# 12.net
KiCad netlist of a schematic drawn in Altium Designer
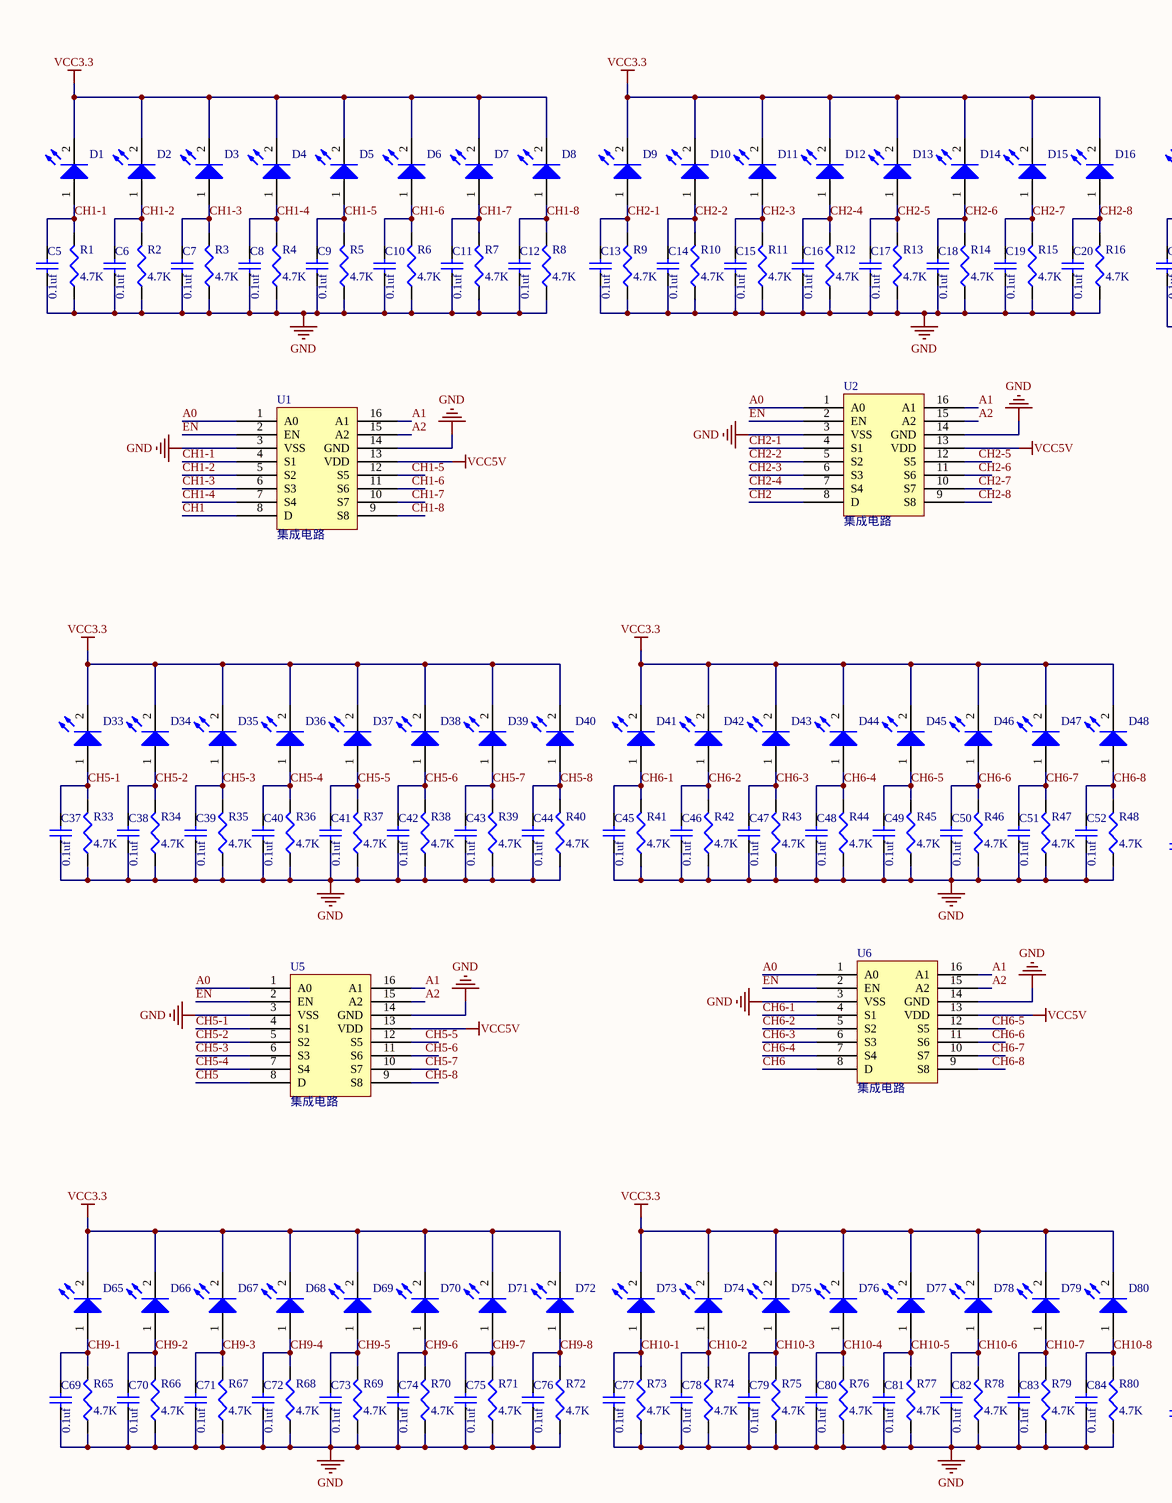
[diagram p0: 数粒机接收板12通道.SchDoc, top left]
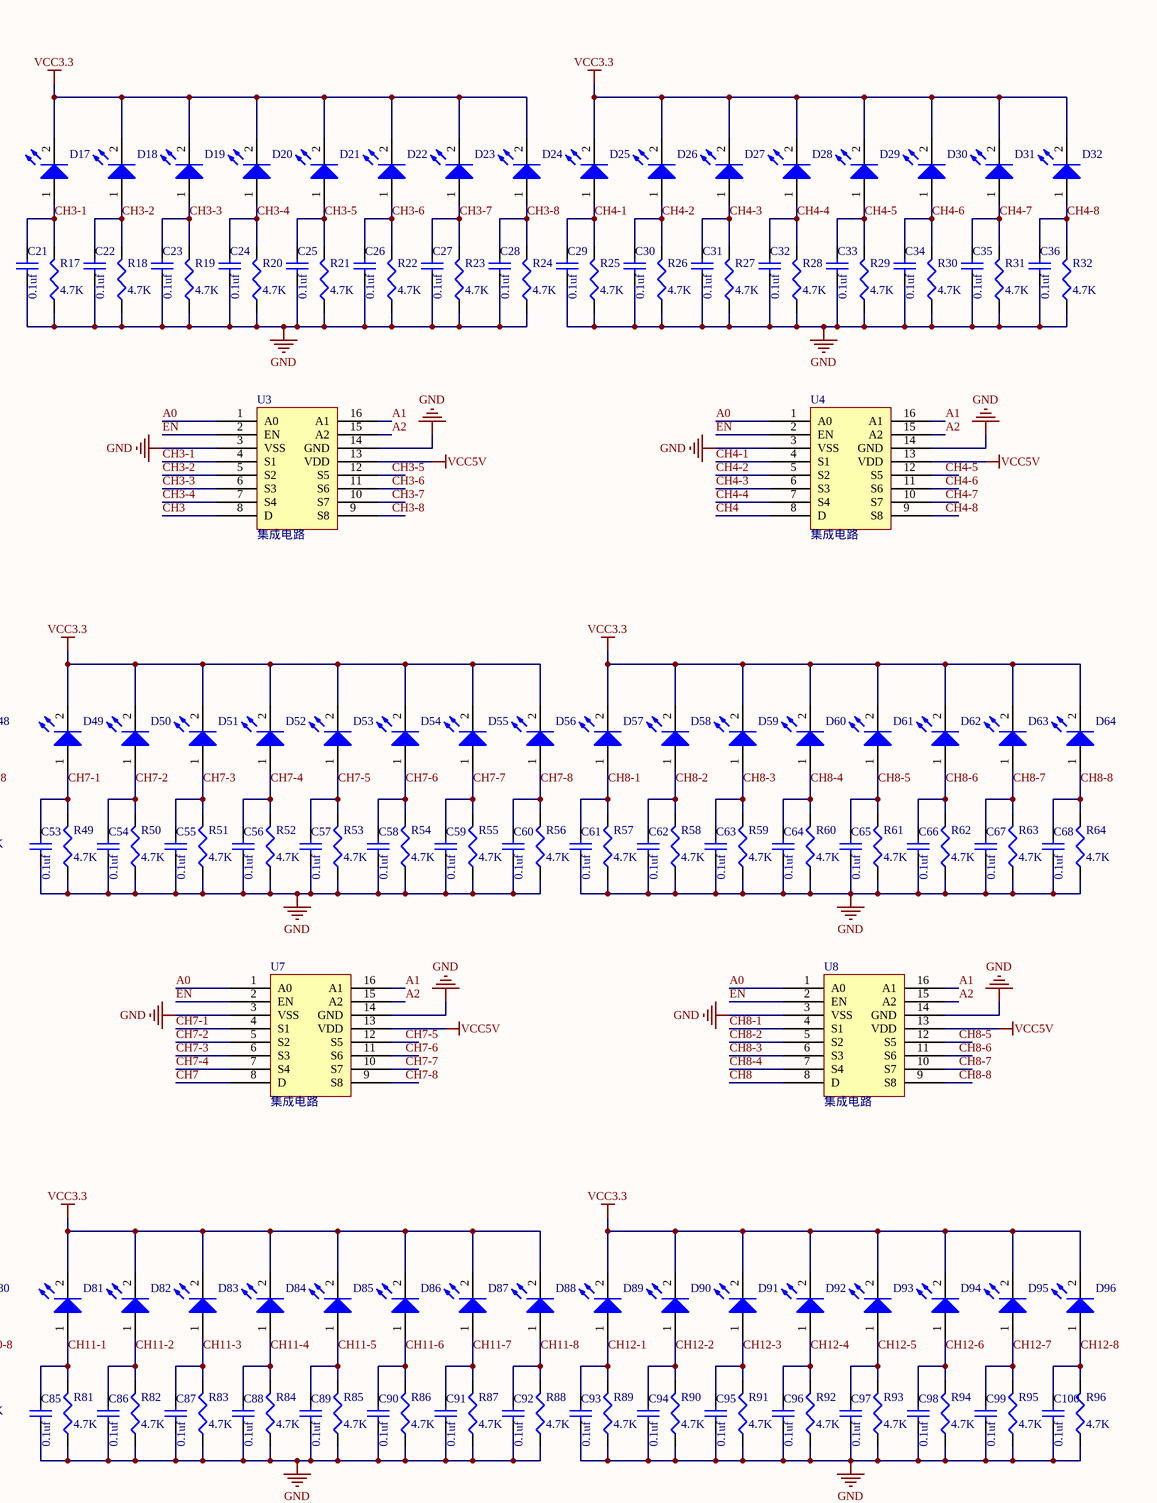
[diagram p1: 数粒机接收板12通道.SchDoc, top right]
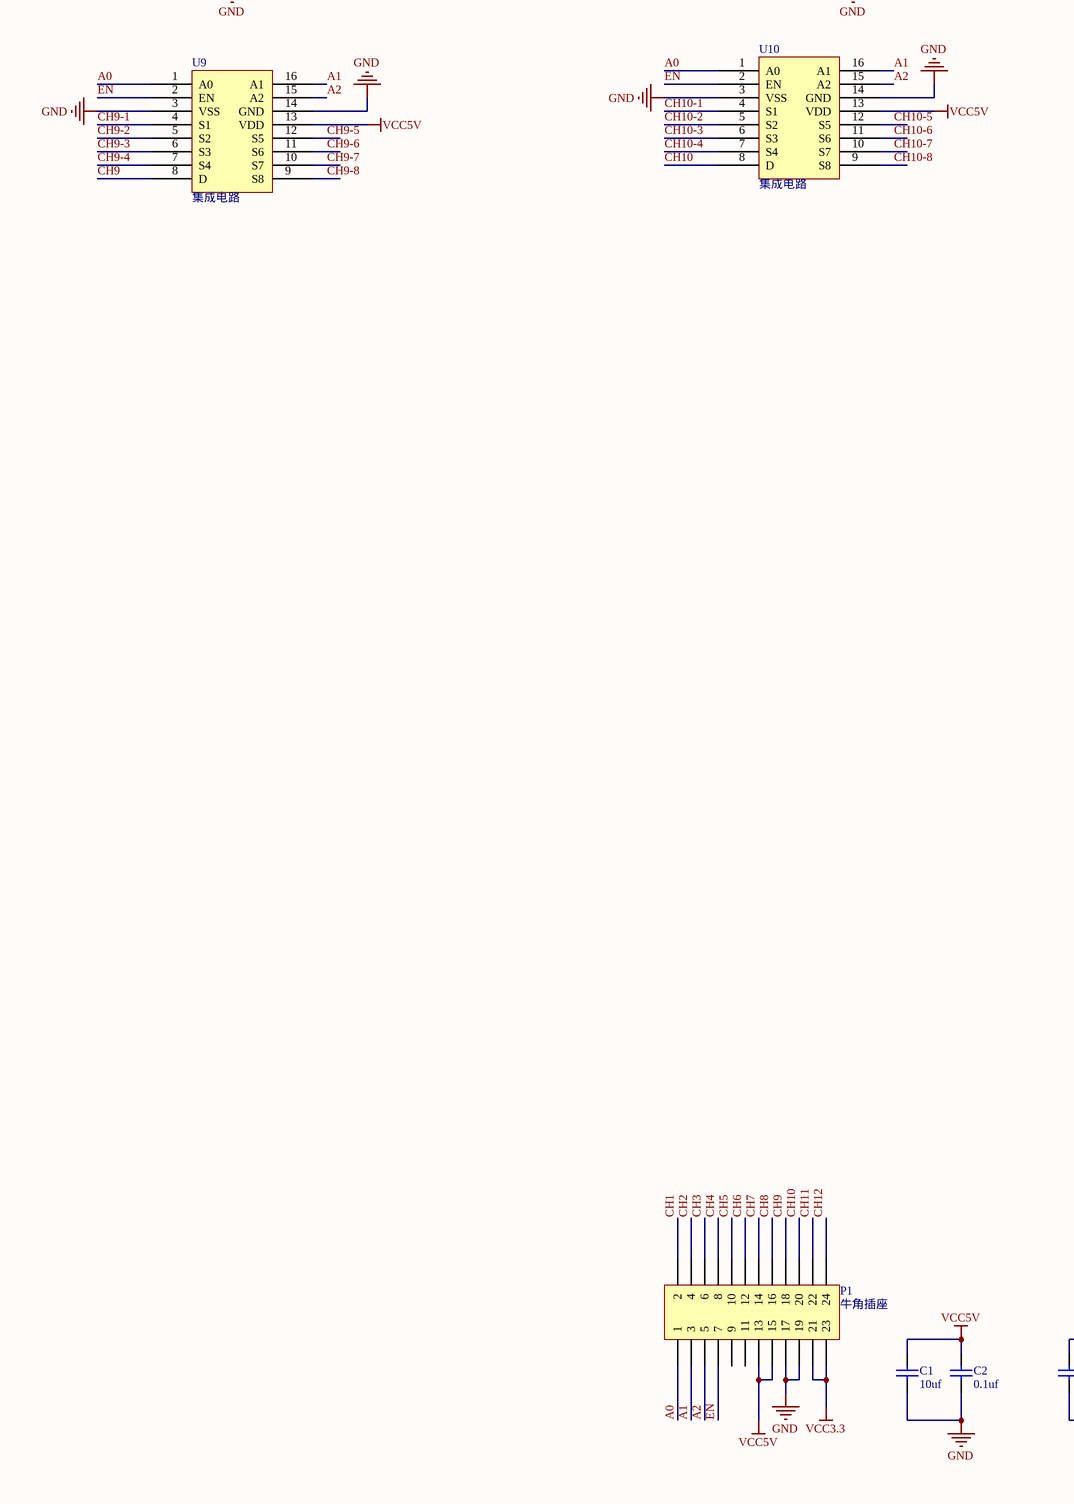
[diagram p2: 数粒机接收板12通道.SchDoc, bottom left]
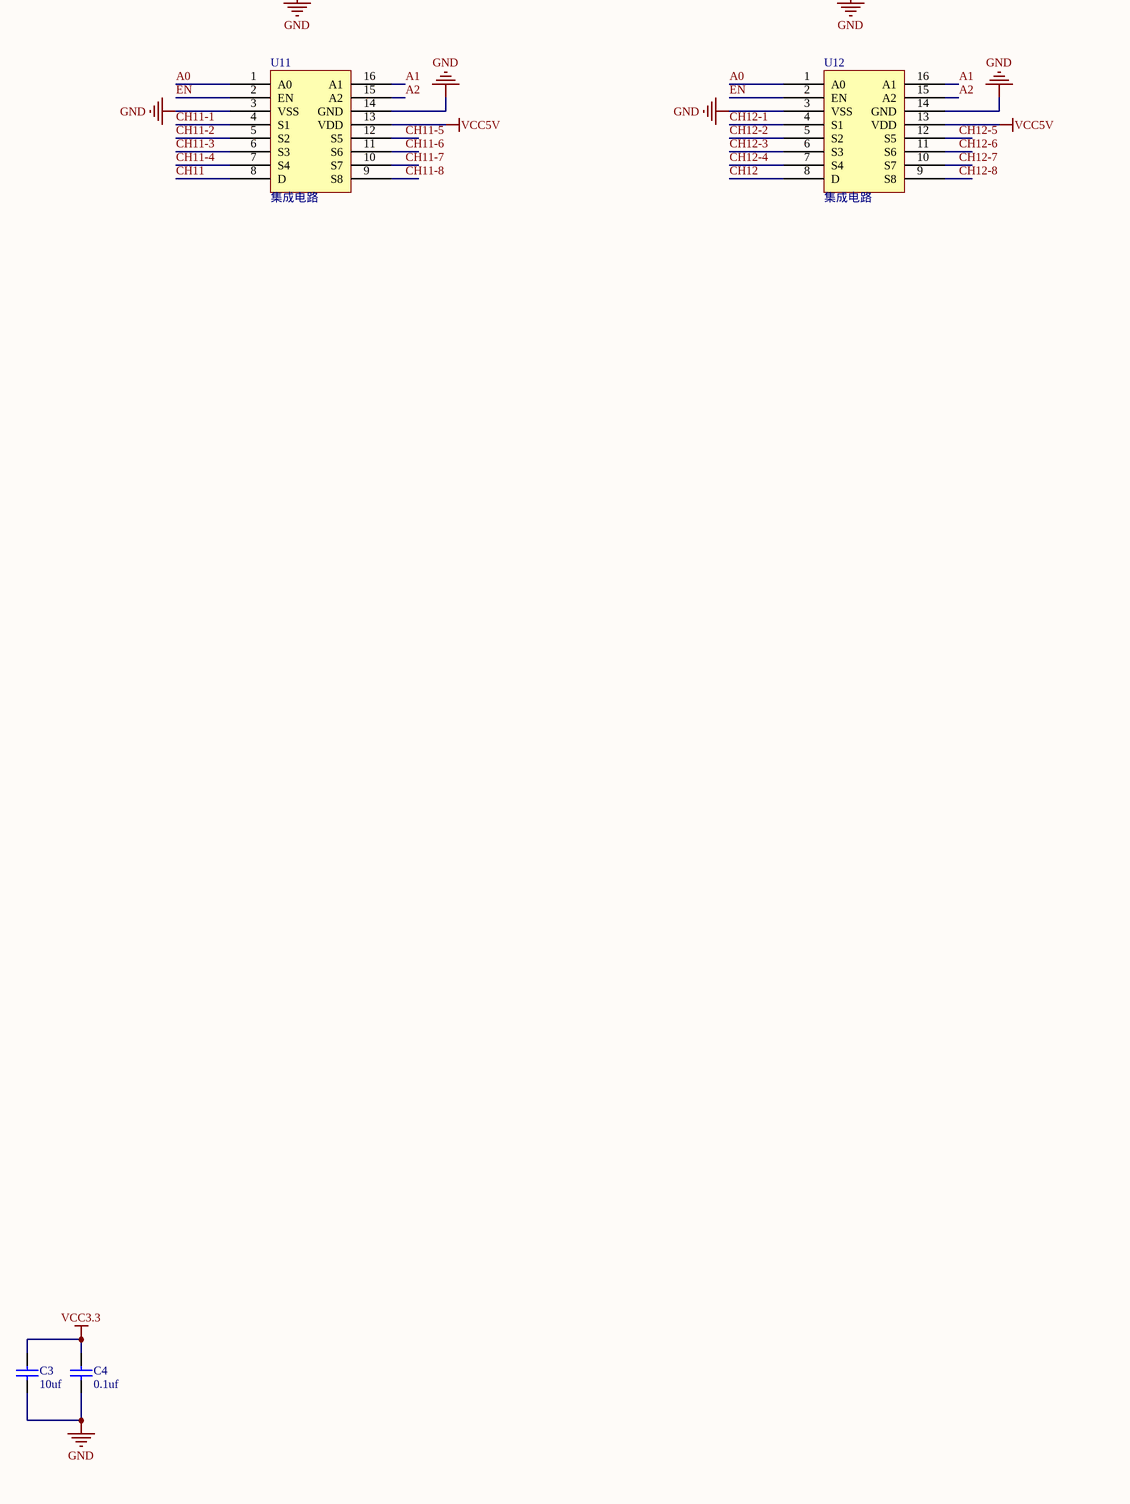
[diagram p3: 数粒机接收板12通道.SchDoc, bottom right]

(export (version "E")
  (design (tool "Eeschema 10.0.6"))
  (components
    (comp (ref "C1")
      (value "10uf")
      (footprint "0805c")
      (description "Capacitor 10uf")
      (fields (field (name "Comment") "贴片电容 10uf") (field (name "PUBLISHER") "Altium Limited"))
      (libsource (lib "Miscellaneous Devices") (part "Cap"))
    )
    (comp (ref "C2")
      (value "0.1uf")
      (footprint "0805c")
      (description "Capacitor 0.1uf")
      (fields (field (name "Comment") "贴片电容 0.1uf") (field (name "PUBLISHER") "Altium Limited"))
      (libsource (lib "Miscellaneous Devices") (part "Cap"))
    )
    (comp (ref "C3")
      (value "10uf")
      (footprint "0805c")
      (description "Capacitor 10uf")
      (fields (field (name "Comment") "贴片电容 10uf") (field (name "PUBLISHER") "Altium Limited"))
      (libsource (lib "Miscellaneous Devices") (part "Cap"))
    )
    (comp (ref "C4")
      (value "0.1uf")
      (footprint "0805c")
      (description "Capacitor 0.1uf")
      (fields (field (name "Comment") "贴片电容 0.1uf") (field (name "PUBLISHER") "Altium Limited"))
      (libsource (lib "Miscellaneous Devices") (part "Cap"))
    )
    (comp (ref "C5")
      (value "0.1uf")
      (footprint "0805c")
      (description "Capacitor 0.1uf")
      (fields (field (name "Comment") "贴片电容 0.1uf") (field (name "PUBLISHER") "Altium Limited"))
      (libsource (lib "Miscellaneous Devices") (part "Cap"))
    )
    (comp (ref "C6")
      (value "0.1uf")
      (footprint "0805c")
      (description "Capacitor 0.1uf")
      (fields (field (name "Comment") "贴片电容 0.1uf") (field (name "PUBLISHER") "Altium Limited"))
      (libsource (lib "Miscellaneous Devices") (part "Cap"))
    )
    (comp (ref "C7")
      (value "0.1uf")
      (footprint "0805c")
      (description "Capacitor 0.1uf")
      (fields (field (name "Comment") "贴片电容 0.1uf") (field (name "PUBLISHER") "Altium Limited"))
      (libsource (lib "Miscellaneous Devices") (part "Cap"))
    )
    (comp (ref "C8")
      (value "0.1uf")
      (footprint "0805c")
      (description "Capacitor 0.1uf")
      (fields (field (name "Comment") "贴片电容 0.1uf") (field (name "PUBLISHER") "Altium Limited"))
      (libsource (lib "Miscellaneous Devices") (part "Cap"))
    )
    (comp (ref "C9")
      (value "0.1uf")
      (footprint "0805c")
      (description "Capacitor 0.1uf")
      (fields (field (name "Comment") "贴片电容 0.1uf") (field (name "PUBLISHER") "Altium Limited"))
      (libsource (lib "Miscellaneous Devices") (part "Cap"))
    )
    (comp (ref "C10")
      (value "0.1uf")
      (footprint "0805c")
      (description "Capacitor 0.1uf")
      (fields (field (name "Comment") "贴片电容 0.1uf") (field (name "PUBLISHER") "Altium Limited"))
      (libsource (lib "Miscellaneous Devices") (part "Cap"))
    )
    (comp (ref "C11")
      (value "0.1uf")
      (footprint "0805c")
      (description "Capacitor 0.1uf")
      (fields (field (name "Comment") "贴片电容 0.1uf") (field (name "PUBLISHER") "Altium Limited"))
      (libsource (lib "Miscellaneous Devices") (part "Cap"))
    )
    (comp (ref "C12")
      (value "0.1uf")
      (footprint "0805c")
      (description "Capacitor 0.1uf")
      (fields (field (name "Comment") "贴片电容 0.1uf") (field (name "PUBLISHER") "Altium Limited"))
      (libsource (lib "Miscellaneous Devices") (part "Cap"))
    )
    (comp (ref "C13")
      (value "0.1uf")
      (footprint "0805c")
      (description "Capacitor 0.1uf")
      (fields (field (name "Comment") "贴片电容 0.1uf") (field (name "PUBLISHER") "Altium Limited"))
      (libsource (lib "Miscellaneous Devices") (part "Cap"))
    )
    (comp (ref "C14")
      (value "0.1uf")
      (footprint "0805c")
      (description "Capacitor 0.1uf")
      (fields (field (name "Comment") "贴片电容 0.1uf") (field (name "PUBLISHER") "Altium Limited"))
      (libsource (lib "Miscellaneous Devices") (part "Cap"))
    )
    (comp (ref "C15")
      (value "0.1uf")
      (footprint "0805c")
      (description "Capacitor 0.1uf")
      (fields (field (name "Comment") "贴片电容 0.1uf") (field (name "PUBLISHER") "Altium Limited"))
      (libsource (lib "Miscellaneous Devices") (part "Cap"))
    )
    (comp (ref "C16")
      (value "0.1uf")
      (footprint "0805c")
      (description "Capacitor 0.1uf")
      (fields (field (name "Comment") "贴片电容 0.1uf") (field (name "PUBLISHER") "Altium Limited"))
      (libsource (lib "Miscellaneous Devices") (part "Cap"))
    )
    (comp (ref "C17")
      (value "0.1uf")
      (footprint "0805c")
      (description "Capacitor 0.1uf")
      (fields (field (name "Comment") "贴片电容 0.1uf") (field (name "PUBLISHER") "Altium Limited"))
      (libsource (lib "Miscellaneous Devices") (part "Cap"))
    )
    (comp (ref "C18")
      (value "0.1uf")
      (footprint "0805c")
      (description "Capacitor 0.1uf")
      (fields (field (name "Comment") "贴片电容 0.1uf") (field (name "PUBLISHER") "Altium Limited"))
      (libsource (lib "Miscellaneous Devices") (part "Cap"))
    )
    (comp (ref "C19")
      (value "0.1uf")
      (footprint "0805c")
      (description "Capacitor 0.1uf")
      (fields (field (name "Comment") "贴片电容 0.1uf") (field (name "PUBLISHER") "Altium Limited"))
      (libsource (lib "Miscellaneous Devices") (part "Cap"))
    )
    (comp (ref "C20")
      (value "0.1uf")
      (footprint "0805c")
      (description "Capacitor 0.1uf")
      (fields (field (name "Comment") "贴片电容 0.1uf") (field (name "PUBLISHER") "Altium Limited"))
      (libsource (lib "Miscellaneous Devices") (part "Cap"))
    )
    (comp (ref "C21")
      (value "0.1uf")
      (footprint "0805c")
      (description "Capacitor 0.1uf")
      (fields (field (name "Comment") "贴片电容 0.1uf") (field (name "PUBLISHER") "Altium Limited"))
      (libsource (lib "Miscellaneous Devices") (part "Cap"))
    )
    (comp (ref "C22")
      (value "0.1uf")
      (footprint "0805c")
      (description "Capacitor 0.1uf")
      (fields (field (name "Comment") "贴片电容 0.1uf") (field (name "PUBLISHER") "Altium Limited"))
      (libsource (lib "Miscellaneous Devices") (part "Cap"))
    )
    (comp (ref "C23")
      (value "0.1uf")
      (footprint "0805c")
      (description "Capacitor 0.1uf")
      (fields (field (name "Comment") "贴片电容 0.1uf") (field (name "PUBLISHER") "Altium Limited"))
      (libsource (lib "Miscellaneous Devices") (part "Cap"))
    )
    (comp (ref "C24")
      (value "0.1uf")
      (footprint "0805c")
      (description "Capacitor 0.1uf")
      (fields (field (name "Comment") "贴片电容 0.1uf") (field (name "PUBLISHER") "Altium Limited"))
      (libsource (lib "Miscellaneous Devices") (part "Cap"))
    )
    (comp (ref "C25")
      (value "0.1uf")
      (footprint "0805c")
      (description "Capacitor 0.1uf")
      (fields (field (name "Comment") "贴片电容 0.1uf") (field (name "PUBLISHER") "Altium Limited"))
      (libsource (lib "Miscellaneous Devices") (part "Cap"))
    )
    (comp (ref "C26")
      (value "0.1uf")
      (footprint "0805c")
      (description "Capacitor 0.1uf")
      (fields (field (name "Comment") "贴片电容 0.1uf") (field (name "PUBLISHER") "Altium Limited"))
      (libsource (lib "Miscellaneous Devices") (part "Cap"))
    )
    (comp (ref "C27")
      (value "0.1uf")
      (footprint "0805c")
      (description "Capacitor 0.1uf")
      (fields (field (name "Comment") "贴片电容 0.1uf") (field (name "PUBLISHER") "Altium Limited"))
      (libsource (lib "Miscellaneous Devices") (part "Cap"))
    )
    (comp (ref "C28")
      (value "0.1uf")
      (footprint "0805c")
      (description "Capacitor 0.1uf")
      (fields (field (name "Comment") "贴片电容 0.1uf") (field (name "PUBLISHER") "Altium Limited"))
      (libsource (lib "Miscellaneous Devices") (part "Cap"))
    )
    (comp (ref "C29")
      (value "0.1uf")
      (footprint "0805c")
      (description "Capacitor 0.1uf")
      (fields (field (name "Comment") "贴片电容 0.1uf") (field (name "PUBLISHER") "Altium Limited"))
      (libsource (lib "Miscellaneous Devices") (part "Cap"))
    )
    (comp (ref "C30")
      (value "0.1uf")
      (footprint "0805c")
      (description "Capacitor 0.1uf")
      (fields (field (name "Comment") "贴片电容 0.1uf") (field (name "PUBLISHER") "Altium Limited"))
      (libsource (lib "Miscellaneous Devices") (part "Cap"))
    )
    (comp (ref "C31")
      (value "0.1uf")
      (footprint "0805c")
      (description "Capacitor 0.1uf")
      (fields (field (name "Comment") "贴片电容 0.1uf") (field (name "PUBLISHER") "Altium Limited"))
      (libsource (lib "Miscellaneous Devices") (part "Cap"))
    )
    (comp (ref "C32")
      (value "0.1uf")
      (footprint "0805c")
      (description "Capacitor 0.1uf")
      (fields (field (name "Comment") "贴片电容 0.1uf") (field (name "PUBLISHER") "Altium Limited"))
      (libsource (lib "Miscellaneous Devices") (part "Cap"))
    )
    (comp (ref "C33")
      (value "0.1uf")
      (footprint "0805c")
      (description "Capacitor 0.1uf")
      (fields (field (name "Comment") "贴片电容 0.1uf") (field (name "PUBLISHER") "Altium Limited"))
      (libsource (lib "Miscellaneous Devices") (part "Cap"))
    )
    (comp (ref "C34")
      (value "0.1uf")
      (footprint "0805c")
      (description "Capacitor 0.1uf")
      (fields (field (name "Comment") "贴片电容 0.1uf") (field (name "PUBLISHER") "Altium Limited"))
      (libsource (lib "Miscellaneous Devices") (part "Cap"))
    )
    (comp (ref "C35")
      (value "0.1uf")
      (footprint "0805c")
      (description "Capacitor 0.1uf")
      (fields (field (name "Comment") "贴片电容 0.1uf") (field (name "PUBLISHER") "Altium Limited"))
      (libsource (lib "Miscellaneous Devices") (part "Cap"))
    )
    (comp (ref "C36")
      (value "0.1uf")
      (footprint "0805c")
      (description "Capacitor 0.1uf")
      (fields (field (name "Comment") "贴片电容 0.1uf") (field (name "PUBLISHER") "Altium Limited"))
      (libsource (lib "Miscellaneous Devices") (part "Cap"))
    )
    (comp (ref "C37")
      (value "0.1uf")
      (footprint "0805c")
      (description "Capacitor 0.1uf")
      (fields (field (name "Comment") "贴片电容 0.1uf") (field (name "PUBLISHER") "Altium Limited"))
      (libsource (lib "Miscellaneous Devices") (part "Cap"))
    )
    (comp (ref "C38")
      (value "0.1uf")
      (footprint "0805c")
      (description "Capacitor 0.1uf")
      (fields (field (name "Comment") "贴片电容 0.1uf") (field (name "PUBLISHER") "Altium Limited"))
      (libsource (lib "Miscellaneous Devices") (part "Cap"))
    )
    (comp (ref "C39")
      (value "0.1uf")
      (footprint "0805c")
      (description "Capacitor 0.1uf")
      (fields (field (name "Comment") "贴片电容 0.1uf") (field (name "PUBLISHER") "Altium Limited"))
      (libsource (lib "Miscellaneous Devices") (part "Cap"))
    )
    (comp (ref "C40")
      (value "0.1uf")
      (footprint "0805c")
      (description "Capacitor 0.1uf")
      (fields (field (name "Comment") "贴片电容 0.1uf") (field (name "PUBLISHER") "Altium Limited"))
      (libsource (lib "Miscellaneous Devices") (part "Cap"))
    )
    (comp (ref "C41")
      (value "0.1uf")
      (footprint "0805c")
      (description "Capacitor 0.1uf")
      (fields (field (name "Comment") "贴片电容 0.1uf") (field (name "PUBLISHER") "Altium Limited"))
      (libsource (lib "Miscellaneous Devices") (part "Cap"))
    )
    (comp (ref "C42")
      (value "0.1uf")
      (footprint "0805c")
      (description "Capacitor 0.1uf")
      (fields (field (name "Comment") "贴片电容 0.1uf") (field (name "PUBLISHER") "Altium Limited"))
      (libsource (lib "Miscellaneous Devices") (part "Cap"))
    )
    (comp (ref "C43")
      (value "0.1uf")
      (footprint "0805c")
      (description "Capacitor 0.1uf")
      (fields (field (name "Comment") "贴片电容 0.1uf") (field (name "PUBLISHER") "Altium Limited"))
      (libsource (lib "Miscellaneous Devices") (part "Cap"))
    )
    (comp (ref "C44")
      (value "0.1uf")
      (footprint "0805c")
      (description "Capacitor 0.1uf")
      (fields (field (name "Comment") "贴片电容 0.1uf") (field (name "PUBLISHER") "Altium Limited"))
      (libsource (lib "Miscellaneous Devices") (part "Cap"))
    )
    (comp (ref "C45")
      (value "0.1uf")
      (footprint "0805c")
      (description "Capacitor 0.1uf")
      (fields (field (name "Comment") "贴片电容 0.1uf") (field (name "PUBLISHER") "Altium Limited"))
      (libsource (lib "Miscellaneous Devices") (part "Cap"))
    )
    (comp (ref "C46")
      (value "0.1uf")
      (footprint "0805c")
      (description "Capacitor 0.1uf")
      (fields (field (name "Comment") "贴片电容 0.1uf") (field (name "PUBLISHER") "Altium Limited"))
      (libsource (lib "Miscellaneous Devices") (part "Cap"))
    )
    (comp (ref "C47")
      (value "0.1uf")
      (footprint "0805c")
      (description "Capacitor 0.1uf")
      (fields (field (name "Comment") "贴片电容 0.1uf") (field (name "PUBLISHER") "Altium Limited"))
      (libsource (lib "Miscellaneous Devices") (part "Cap"))
    )
    (comp (ref "C48")
      (value "0.1uf")
      (footprint "0805c")
      (description "Capacitor 0.1uf")
      (fields (field (name "Comment") "贴片电容 0.1uf") (field (name "PUBLISHER") "Altium Limited"))
      (libsource (lib "Miscellaneous Devices") (part "Cap"))
    )
    (comp (ref "C49")
      (value "0.1uf")
      (footprint "0805c")
      (description "Capacitor 0.1uf")
      (fields (field (name "Comment") "贴片电容 0.1uf") (field (name "PUBLISHER") "Altium Limited"))
      (libsource (lib "Miscellaneous Devices") (part "Cap"))
    )
    (comp (ref "C50")
      (value "0.1uf")
      (footprint "0805c")
      (description "Capacitor 0.1uf")
      (fields (field (name "Comment") "贴片电容 0.1uf") (field (name "PUBLISHER") "Altium Limited"))
      (libsource (lib "Miscellaneous Devices") (part "Cap"))
    )
    (comp (ref "C51")
      (value "0.1uf")
      (footprint "0805c")
      (description "Capacitor 0.1uf")
      (fields (field (name "Comment") "贴片电容 0.1uf") (field (name "PUBLISHER") "Altium Limited"))
      (libsource (lib "Miscellaneous Devices") (part "Cap"))
    )
    (comp (ref "C52")
      (value "0.1uf")
      (footprint "0805c")
      (description "Capacitor 0.1uf")
      (fields (field (name "Comment") "贴片电容 0.1uf") (field (name "PUBLISHER") "Altium Limited"))
      (libsource (lib "Miscellaneous Devices") (part "Cap"))
    )
    (comp (ref "C53")
      (value "0.1uf")
      (footprint "0805c")
      (description "Capacitor 0.1uf")
      (fields (field (name "Comment") "贴片电容 0.1uf") (field (name "PUBLISHER") "Altium Limited"))
      (libsource (lib "Miscellaneous Devices") (part "Cap"))
    )
    (comp (ref "C54")
      (value "0.1uf")
      (footprint "0805c")
      (description "Capacitor 0.1uf")
      (fields (field (name "Comment") "贴片电容 0.1uf") (field (name "PUBLISHER") "Altium Limited"))
      (libsource (lib "Miscellaneous Devices") (part "Cap"))
    )
    (comp (ref "C55")
      (value "0.1uf")
      (footprint "0805c")
      (description "Capacitor 0.1uf")
      (fields (field (name "Comment") "贴片电容 0.1uf") (field (name "PUBLISHER") "Altium Limited"))
      (libsource (lib "Miscellaneous Devices") (part "Cap"))
    )
    (comp (ref "C56")
      (value "0.1uf")
      (footprint "0805c")
      (description "Capacitor 0.1uf")
      (fields (field (name "Comment") "贴片电容 0.1uf") (field (name "PUBLISHER") "Altium Limited"))
      (libsource (lib "Miscellaneous Devices") (part "Cap"))
    )
    (comp (ref "C57")
      (value "0.1uf")
      (footprint "0805c")
      (description "Capacitor 0.1uf")
      (fields (field (name "Comment") "贴片电容 0.1uf") (field (name "PUBLISHER") "Altium Limited"))
      (libsource (lib "Miscellaneous Devices") (part "Cap"))
    )
    (comp (ref "C58")
      (value "0.1uf")
      (footprint "0805c")
      (description "Capacitor 0.1uf")
      (fields (field (name "Comment") "贴片电容 0.1uf") (field (name "PUBLISHER") "Altium Limited"))
      (libsource (lib "Miscellaneous Devices") (part "Cap"))
    )
    (comp (ref "C59")
      (value "0.1uf")
      (footprint "0805c")
      (description "Capacitor 0.1uf")
      (fields (field (name "Comment") "贴片电容 0.1uf") (field (name "PUBLISHER") "Altium Limited"))
      (libsource (lib "Miscellaneous Devices") (part "Cap"))
    )
    (comp (ref "C60")
      (value "0.1uf")
      (footprint "0805c")
      (description "Capacitor 0.1uf")
      (fields (field (name "Comment") "贴片电容 0.1uf") (field (name "PUBLISHER") "Altium Limited"))
      (libsource (lib "Miscellaneous Devices") (part "Cap"))
    )
    (comp (ref "C61")
      (value "0.1uf")
      (footprint "0805c")
      (description "Capacitor 0.1uf")
      (fields (field (name "Comment") "贴片电容 0.1uf") (field (name "PUBLISHER") "Altium Limited"))
      (libsource (lib "Miscellaneous Devices") (part "Cap"))
    )
    (comp (ref "C62")
      (value "0.1uf")
      (footprint "0805c")
      (description "Capacitor 0.1uf")
      (fields (field (name "Comment") "贴片电容 0.1uf") (field (name "PUBLISHER") "Altium Limited"))
      (libsource (lib "Miscellaneous Devices") (part "Cap"))
    )
    (comp (ref "C63")
      (value "0.1uf")
      (footprint "0805c")
      (description "Capacitor 0.1uf")
      (fields (field (name "Comment") "贴片电容 0.1uf") (field (name "PUBLISHER") "Altium Limited"))
      (libsource (lib "Miscellaneous Devices") (part "Cap"))
    )
    (comp (ref "C64")
      (value "0.1uf")
      (footprint "0805c")
      (description "Capacitor 0.1uf")
      (fields (field (name "Comment") "贴片电容 0.1uf") (field (name "PUBLISHER") "Altium Limited"))
      (libsource (lib "Miscellaneous Devices") (part "Cap"))
    )
    (comp (ref "C65")
      (value "0.1uf")
      (footprint "0805c")
      (description "Capacitor 0.1uf")
      (fields (field (name "Comment") "贴片电容 0.1uf") (field (name "PUBLISHER") "Altium Limited"))
      (libsource (lib "Miscellaneous Devices") (part "Cap"))
    )
    (comp (ref "C66")
      (value "0.1uf")
      (footprint "0805c")
      (description "Capacitor 0.1uf")
      (fields (field (name "Comment") "贴片电容 0.1uf") (field (name "PUBLISHER") "Altium Limited"))
      (libsource (lib "Miscellaneous Devices") (part "Cap"))
    )
    (comp (ref "C67")
      (value "0.1uf")
      (footprint "0805c")
      (description "Capacitor 0.1uf")
      (fields (field (name "Comment") "贴片电容 0.1uf") (field (name "PUBLISHER") "Altium Limited"))
      (libsource (lib "Miscellaneous Devices") (part "Cap"))
    )
    (comp (ref "C68")
      (value "0.1uf")
      (footprint "0805c")
      (description "Capacitor 0.1uf")
      (fields (field (name "Comment") "贴片电容 0.1uf") (field (name "PUBLISHER") "Altium Limited"))
      (libsource (lib "Miscellaneous Devices") (part "Cap"))
    )
    (comp (ref "C69")
      (value "0.1uf")
      (footprint "0805c")
      (description "Capacitor 0.1uf")
      (fields (field (name "Comment") "贴片电容 0.1uf") (field (name "PUBLISHER") "Altium Limited"))
      (libsource (lib "Miscellaneous Devices") (part "Cap"))
    )
    (comp (ref "C70")
      (value "0.1uf")
      (footprint "0805c")
      (description "Capacitor 0.1uf")
      (fields (field (name "Comment") "贴片电容 0.1uf") (field (name "PUBLISHER") "Altium Limited"))
      (libsource (lib "Miscellaneous Devices") (part "Cap"))
    )
    (comp (ref "C71")
      (value "0.1uf")
      (footprint "0805c")
      (description "Capacitor 0.1uf")
      (fields (field (name "Comment") "贴片电容 0.1uf") (field (name "PUBLISHER") "Altium Limited"))
      (libsource (lib "Miscellaneous Devices") (part "Cap"))
    )
    (comp (ref "C72")
      (value "0.1uf")
      (footprint "0805c")
      (description "Capacitor 0.1uf")
      (fields (field (name "Comment") "贴片电容 0.1uf") (field (name "PUBLISHER") "Altium Limited"))
      (libsource (lib "Miscellaneous Devices") (part "Cap"))
    )
    (comp (ref "C73")
      (value "0.1uf")
      (footprint "0805c")
      (description "Capacitor 0.1uf")
      (fields (field (name "Comment") "贴片电容 0.1uf") (field (name "PUBLISHER") "Altium Limited"))
      (libsource (lib "Miscellaneous Devices") (part "Cap"))
    )
    (comp (ref "C74")
      (value "0.1uf")
      (footprint "0805c")
      (description "Capacitor 0.1uf")
      (fields (field (name "Comment") "贴片电容 0.1uf") (field (name "PUBLISHER") "Altium Limited"))
      (libsource (lib "Miscellaneous Devices") (part "Cap"))
    )
    (comp (ref "C75")
      (value "0.1uf")
      (footprint "0805c")
      (description "Capacitor 0.1uf")
      (fields (field (name "Comment") "贴片电容 0.1uf") (field (name "PUBLISHER") "Altium Limited"))
      (libsource (lib "Miscellaneous Devices") (part "Cap"))
    )
    (comp (ref "C76")
      (value "0.1uf")
      (footprint "0805c")
      (description "Capacitor 0.1uf")
      (fields (field (name "Comment") "贴片电容 0.1uf") (field (name "PUBLISHER") "Altium Limited"))
      (libsource (lib "Miscellaneous Devices") (part "Cap"))
    )
    (comp (ref "C77")
      (value "0.1uf")
      (footprint "0805c")
      (description "Capacitor 0.1uf")
      (fields (field (name "Comment") "贴片电容 0.1uf") (field (name "PUBLISHER") "Altium Limited"))
      (libsource (lib "Miscellaneous Devices") (part "Cap"))
    )
    (comp (ref "C78")
      (value "0.1uf")
      (footprint "0805c")
      (description "Capacitor 0.1uf")
      (fields (field (name "Comment") "贴片电容 0.1uf") (field (name "PUBLISHER") "Altium Limited"))
      (libsource (lib "Miscellaneous Devices") (part "Cap"))
    )
    (comp (ref "C79")
      (value "0.1uf")
      (footprint "0805c")
      (description "Capacitor 0.1uf")
      (fields (field (name "Comment") "贴片电容 0.1uf") (field (name "PUBLISHER") "Altium Limited"))
      (libsource (lib "Miscellaneous Devices") (part "Cap"))
    )
    (comp (ref "C80")
      (value "0.1uf")
      (footprint "0805c")
      (description "Capacitor 0.1uf")
      (fields (field (name "Comment") "贴片电容 0.1uf") (field (name "PUBLISHER") "Altium Limited"))
      (libsource (lib "Miscellaneous Devices") (part "Cap"))
    )
    (comp (ref "C81")
      (value "0.1uf")
      (footprint "0805c")
      (description "Capacitor 0.1uf")
      (fields (field (name "Comment") "贴片电容 0.1uf") (field (name "PUBLISHER") "Altium Limited"))
      (libsource (lib "Miscellaneous Devices") (part "Cap"))
    )
    (comp (ref "C82")
      (value "0.1uf")
      (footprint "0805c")
      (description "Capacitor 0.1uf")
      (fields (field (name "Comment") "贴片电容 0.1uf") (field (name "PUBLISHER") "Altium Limited"))
      (libsource (lib "Miscellaneous Devices") (part "Cap"))
    )
    (comp (ref "C83")
      (value "0.1uf")
      (footprint "0805c")
      (description "Capacitor 0.1uf")
      (fields (field (name "Comment") "贴片电容 0.1uf") (field (name "PUBLISHER") "Altium Limited"))
      (libsource (lib "Miscellaneous Devices") (part "Cap"))
    )
    (comp (ref "C84")
      (value "0.1uf")
      (footprint "0805c")
      (description "Capacitor 0.1uf")
      (fields (field (name "Comment") "贴片电容 0.1uf") (field (name "PUBLISHER") "Altium Limited"))
      (libsource (lib "Miscellaneous Devices") (part "Cap"))
    )
    (comp (ref "C85")
      (value "0.1uf")
      (footprint "0805c")
      (description "Capacitor 0.1uf")
      (fields (field (name "Comment") "贴片电容 0.1uf") (field (name "PUBLISHER") "Altium Limited"))
      (libsource (lib "Miscellaneous Devices") (part "Cap"))
    )
    (comp (ref "C86")
      (value "0.1uf")
      (footprint "0805c")
      (description "Capacitor 0.1uf")
      (fields (field (name "Comment") "贴片电容 0.1uf") (field (name "PUBLISHER") "Altium Limited"))
      (libsource (lib "Miscellaneous Devices") (part "Cap"))
    )
    (comp (ref "C87")
      (value "0.1uf")
      (footprint "0805c")
      (description "Capacitor 0.1uf")
      (fields (field (name "Comment") "贴片电容 0.1uf") (field (name "PUBLISHER") "Altium Limited"))
      (libsource (lib "Miscellaneous Devices") (part "Cap"))
    )
    (comp (ref "C88")
      (value "0.1uf")
      (footprint "0805c")
      (description "Capacitor 0.1uf")
      (fields (field (name "Comment") "贴片电容 0.1uf") (field (name "PUBLISHER") "Altium Limited"))
      (libsource (lib "Miscellaneous Devices") (part "Cap"))
    )
    (comp (ref "C89")
      (value "0.1uf")
      (footprint "0805c")
      (description "Capacitor 0.1uf")
      (fields (field (name "Comment") "贴片电容 0.1uf") (field (name "PUBLISHER") "Altium Limited"))
      (libsource (lib "Miscellaneous Devices") (part "Cap"))
    )
    (comp (ref "C90")
      (value "0.1uf")
      (footprint "0805c")
      (description "Capacitor 0.1uf")
      (fields (field (name "Comment") "贴片电容 0.1uf") (field (name "PUBLISHER") "Altium Limited"))
      (libsource (lib "Miscellaneous Devices") (part "Cap"))
    )
    (comp (ref "C91")
      (value "0.1uf")
      (footprint "0805c")
      (description "Capacitor 0.1uf")
      (fields (field (name "Comment") "贴片电容 0.1uf") (field (name "PUBLISHER") "Altium Limited"))
      (libsource (lib "Miscellaneous Devices") (part "Cap"))
    )
    (comp (ref "C92")
      (value "0.1uf")
      (footprint "0805c")
      (description "Capacitor 0.1uf")
      (fields (field (name "Comment") "贴片电容 0.1uf") (field (name "PUBLISHER") "Altium Limited"))
      (libsource (lib "Miscellaneous Devices") (part "Cap"))
    )
    (comp (ref "C93")
      (value "0.1uf")
      (footprint "0805c")
      (description "Capacitor 0.1uf")
      (fields (field (name "Comment") "贴片电容 0.1uf") (field (name "PUBLISHER") "Altium Limited"))
      (libsource (lib "Miscellaneous Devices") (part "Cap"))
    )
    (comp (ref "C94")
      (value "0.1uf")
      (footprint "0805c")
      (description "Capacitor 0.1uf")
      (fields (field (name "Comment") "贴片电容 0.1uf") (field (name "PUBLISHER") "Altium Limited"))
      (libsource (lib "Miscellaneous Devices") (part "Cap"))
    )
    (comp (ref "C95")
      (value "0.1uf")
      (footprint "0805c")
      (description "Capacitor 0.1uf")
      (fields (field (name "Comment") "贴片电容 0.1uf") (field (name "PUBLISHER") "Altium Limited"))
      (libsource (lib "Miscellaneous Devices") (part "Cap"))
    )
    (comp (ref "C96")
      (value "0.1uf")
      (footprint "0805c")
      (description "Capacitor 0.1uf")
      (fields (field (name "Comment") "贴片电容 0.1uf") (field (name "PUBLISHER") "Altium Limited"))
      (libsource (lib "Miscellaneous Devices") (part "Cap"))
    )
    (comp (ref "C97")
      (value "0.1uf")
      (footprint "0805c")
      (description "Capacitor 0.1uf")
      (fields (field (name "Comment") "贴片电容 0.1uf") (field (name "PUBLISHER") "Altium Limited"))
      (libsource (lib "Miscellaneous Devices") (part "Cap"))
    )
    (comp (ref "C98")
      (value "0.1uf")
      (footprint "0805c")
      (description "Capacitor 0.1uf")
      (fields (field (name "Comment") "贴片电容 0.1uf") (field (name "PUBLISHER") "Altium Limited"))
      (libsource (lib "Miscellaneous Devices") (part "Cap"))
    )
    (comp (ref "C99")
      (value "0.1uf")
      (footprint "0805c")
      (description "Capacitor 0.1uf")
      (fields (field (name "Comment") "贴片电容 0.1uf") (field (name "PUBLISHER") "Altium Limited"))
      (libsource (lib "Miscellaneous Devices") (part "Cap"))
    )
    (comp (ref "C100")
      (value "0.1uf")
      (footprint "0805c")
      (description "Capacitor 0.1uf")
      (fields (field (name "Comment") "贴片电容 0.1uf") (field (name "PUBLISHER") "Altium Limited"))
      (libsource (lib "Miscellaneous Devices") (part "Cap"))
    )
    (comp (ref "D1")
      (value "红外接收珠子")
      (footprint "jieshou1206")
      (description "PD15-21B/TR8")
      (fields (field (name "PUBLISHER") "Altium Limited"))
      (libsource (lib "Miscellaneous Devices") (part "PD15-21B/TR8"))
    )
    (comp (ref "D2")
      (value "红外接收珠子")
      (footprint "jieshou1206")
      (description "PD15-21B/TR8")
      (fields (field (name "PUBLISHER") "Altium Limited"))
      (libsource (lib "Miscellaneous Devices") (part "PD15-21B/TR8"))
    )
    (comp (ref "D3")
      (value "红外接收珠子")
      (footprint "jieshou1206")
      (description "PD15-21B/TR8")
      (fields (field (name "PUBLISHER") "Altium Limited"))
      (libsource (lib "Miscellaneous Devices") (part "PD15-21B/TR8"))
    )
    (comp (ref "D4")
      (value "红外接收珠子")
      (footprint "jieshou1206")
      (description "PD15-21B/TR8")
      (fields (field (name "PUBLISHER") "Altium Limited"))
      (libsource (lib "Miscellaneous Devices") (part "PD15-21B/TR8"))
    )
    (comp (ref "D5")
      (value "红外接收珠子")
      (footprint "jieshou1206")
      (description "PD15-21B/TR8")
      (fields (field (name "PUBLISHER") "Altium Limited"))
      (libsource (lib "Miscellaneous Devices") (part "PD15-21B/TR8"))
    )
    (comp (ref "D6")
      (value "红外接收珠子")
      (footprint "jieshou1206")
      (description "PD15-21B/TR8")
      (fields (field (name "PUBLISHER") "Altium Limited"))
      (libsource (lib "Miscellaneous Devices") (part "PD15-21B/TR8"))
    )
    (comp (ref "D7")
      (value "红外接收珠子")
      (footprint "jieshou1206")
      (description "PD15-21B/TR8")
      (fields (field (name "PUBLISHER") "Altium Limited"))
      (libsource (lib "Miscellaneous Devices") (part "PD15-21B/TR8"))
    )
    (comp (ref "D8")
      (value "红外接收珠子")
      (footprint "jieshou1206")
      (description "PD15-21B/TR8")
      (fields (field (name "PUBLISHER") "Altium Limited"))
      (libsource (lib "Miscellaneous Devices") (part "PD15-21B/TR8"))
    )
    (comp (ref "D9")
      (value "红外接收珠子")
      (footprint "jieshou1206")
      (description "PD15-21B/TR8")
      (fields (field (name "PUBLISHER") "Altium Limited"))
      (libsource (lib "Miscellaneous Devices") (part "PD15-21B/TR8"))
    )
    (comp (ref "D10")
      (value "红外接收珠子")
      (footprint "jieshou1206")
      (description "PD15-21B/TR8")
      (fields (field (name "PUBLISHER") "Altium Limited"))
      (libsource (lib "Miscellaneous Devices") (part "PD15-21B/TR8"))
    )
    (comp (ref "D11")
      (value "红外接收珠子")
      (footprint "jieshou1206")
      (description "PD15-21B/TR8")
      (fields (field (name "PUBLISHER") "Altium Limited"))
      (libsource (lib "Miscellaneous Devices") (part "PD15-21B/TR8"))
    )
    (comp (ref "D12")
      (value "红外接收珠子")
      (footprint "jieshou1206")
      (description "PD15-21B/TR8")
      (fields (field (name "PUBLISHER") "Altium Limited"))
      (libsource (lib "Miscellaneous Devices") (part "PD15-21B/TR8"))
    )
    (comp (ref "D13")
      (value "红外接收珠子")
      (footprint "jieshou1206")
      (description "PD15-21B/TR8")
      (fields (field (name "PUBLISHER") "Altium Limited"))
      (libsource (lib "Miscellaneous Devices") (part "PD15-21B/TR8"))
    )
    (comp (ref "D14")
      (value "红外接收珠子")
      (footprint "jieshou1206")
      (description "PD15-21B/TR8")
      (fields (field (name "PUBLISHER") "Altium Limited"))
      (libsource (lib "Miscellaneous Devices") (part "PD15-21B/TR8"))
    )
    (comp (ref "D15")
      (value "红外接收珠子")
      (footprint "jieshou1206")
      (description "PD15-21B/TR8")
      (fields (field (name "PUBLISHER") "Altium Limited"))
      (libsource (lib "Miscellaneous Devices") (part "PD15-21B/TR8"))
    )
    (comp (ref "D16")
      (value "红外接收珠子")
      (footprint "jieshou1206")
      (description "PD15-21B/TR8")
      (fields (field (name "PUBLISHER") "Altium Limited"))
      (libsource (lib "Miscellaneous Devices") (part "PD15-21B/TR8"))
    )
    (comp (ref "D17")
      (value "红外接收珠子")
      (footprint "jieshou1206")
      (description "PD15-21B/TR8")
      (fields (field (name "PUBLISHER") "Altium Limited"))
      (libsource (lib "Miscellaneous Devices") (part "PD15-21B/TR8"))
    )
    (comp (ref "D18")
      (value "红外接收珠子")
      (footprint "jieshou1206")
      (description "PD15-21B/TR8")
      (fields (field (name "PUBLISHER") "Altium Limited"))
      (libsource (lib "Miscellaneous Devices") (part "PD15-21B/TR8"))
    )
    (comp (ref "D19")
      (value "红外接收珠子")
      (footprint "jieshou1206")
      (description "PD15-21B/TR8")
      (fields (field (name "PUBLISHER") "Altium Limited"))
      (libsource (lib "Miscellaneous Devices") (part "PD15-21B/TR8"))
    )
    (comp (ref "D20")
      (value "红外接收珠子")
      (footprint "jieshou1206")
      (description "PD15-21B/TR8")
      (fields (field (name "PUBLISHER") "Altium Limited"))
      (libsource (lib "Miscellaneous Devices") (part "PD15-21B/TR8"))
    )
    (comp (ref "D21")
      (value "红外接收珠子")
      (footprint "jieshou1206")
      (description "PD15-21B/TR8")
      (fields (field (name "PUBLISHER") "Altium Limited"))
      (libsource (lib "Miscellaneous Devices") (part "PD15-21B/TR8"))
    )
    (comp (ref "D22")
      (value "红外接收珠子")
      (footprint "jieshou1206")
      (description "PD15-21B/TR8")
      (fields (field (name "PUBLISHER") "Altium Limited"))
      (libsource (lib "Miscellaneous Devices") (part "PD15-21B/TR8"))
    )
    (comp (ref "D23")
      (value "红外接收珠子")
      (footprint "jieshou1206")
      (description "PD15-21B/TR8")
      (fields (field (name "PUBLISHER") "Altium Limited"))
      (libsource (lib "Miscellaneous Devices") (part "PD15-21B/TR8"))
    )
    (comp (ref "D24")
      (value "红外接收珠子")
      (footprint "jieshou1206")
      (description "PD15-21B/TR8")
      (fields (field (name "PUBLISHER") "Altium Limited"))
      (libsource (lib "Miscellaneous Devices") (part "PD15-21B/TR8"))
    )
    (comp (ref "D25")
      (value "红外接收珠子")
      (footprint "jieshou1206")
      (description "PD15-21B/TR8")
      (fields (field (name "PUBLISHER") "Altium Limited"))
      (libsource (lib "Miscellaneous Devices") (part "PD15-21B/TR8"))
    )
    (comp (ref "D26")
      (value "红外接收珠子")
      (footprint "jieshou1206")
      (description "PD15-21B/TR8")
      (fields (field (name "PUBLISHER") "Altium Limited"))
      (libsource (lib "Miscellaneous Devices") (part "PD15-21B/TR8"))
    )
    (comp (ref "D27")
      (value "红外接收珠子")
      (footprint "jieshou1206")
      (description "PD15-21B/TR8")
      (fields (field (name "PUBLISHER") "Altium Limited"))
      (libsource (lib "Miscellaneous Devices") (part "PD15-21B/TR8"))
    )
    (comp (ref "D28")
      (value "红外接收珠子")
      (footprint "jieshou1206")
      (description "PD15-21B/TR8")
      (fields (field (name "PUBLISHER") "Altium Limited"))
      (libsource (lib "Miscellaneous Devices") (part "PD15-21B/TR8"))
    )
    (comp (ref "D29")
      (value "红外接收珠子")
      (footprint "jieshou1206")
      (description "PD15-21B/TR8")
      (fields (field (name "PUBLISHER") "Altium Limited"))
      (libsource (lib "Miscellaneous Devices") (part "PD15-21B/TR8"))
    )
    (comp (ref "D30")
      (value "红外接收珠子")
      (footprint "jieshou1206")
      (description "PD15-21B/TR8")
      (fields (field (name "PUBLISHER") "Altium Limited"))
      (libsource (lib "Miscellaneous Devices") (part "PD15-21B/TR8"))
    )
    (comp (ref "D31")
      (value "红外接收珠子")
      (footprint "jieshou1206")
      (description "PD15-21B/TR8")
      (fields (field (name "PUBLISHER") "Altium Limited"))
      (libsource (lib "Miscellaneous Devices") (part "PD15-21B/TR8"))
    )
    (comp (ref "D32")
      (value "红外接收珠子")
      (footprint "jieshou1206")
      (description "PD15-21B/TR8")
      (fields (field (name "PUBLISHER") "Altium Limited"))
      (libsource (lib "Miscellaneous Devices") (part "PD15-21B/TR8"))
    )
    (comp (ref "D33")
      (value "红外接收珠子")
      (footprint "jieshou1206")
      (description "PD15-21B/TR8")
      (fields (field (name "PUBLISHER") "Altium Limited"))
      (libsource (lib "Miscellaneous Devices") (part "PD15-21B/TR8"))
    )
    (comp (ref "D34")
      (value "红外接收珠子")
      (footprint "jieshou1206")
      (description "PD15-21B/TR8")
      (fields (field (name "PUBLISHER") "Altium Limited"))
      (libsource (lib "Miscellaneous Devices") (part "PD15-21B/TR8"))
    )
    (comp (ref "D35")
      (value "红外接收珠子")
      (footprint "jieshou1206")
      (description "PD15-21B/TR8")
      (fields (field (name "PUBLISHER") "Altium Limited"))
      (libsource (lib "Miscellaneous Devices") (part "PD15-21B/TR8"))
    )
    (comp (ref "D36")
      (value "红外接收珠子")
      (footprint "jieshou1206")
      (description "PD15-21B/TR8")
      (fields (field (name "PUBLISHER") "Altium Limited"))
      (libsource (lib "Miscellaneous Devices") (part "PD15-21B/TR8"))
    )
    (comp (ref "D37")
      (value "红外接收珠子")
      (footprint "jieshou1206")
      (description "PD15-21B/TR8")
      (fields (field (name "PUBLISHER") "Altium Limited"))
      (libsource (lib "Miscellaneous Devices") (part "PD15-21B/TR8"))
    )
    (comp (ref "D38")
      (value "红外接收珠子")
      (footprint "jieshou1206")
      (description "PD15-21B/TR8")
      (fields (field (name "PUBLISHER") "Altium Limited"))
      (libsource (lib "Miscellaneous Devices") (part "PD15-21B/TR8"))
    )
    (comp (ref "D39")
      (value "红外接收珠子")
      (footprint "jieshou1206")
      (description "PD15-21B/TR8")
      (fields (field (name "PUBLISHER") "Altium Limited"))
      (libsource (lib "Miscellaneous Devices") (part "PD15-21B/TR8"))
    )
    (comp (ref "D40")
      (value "红外接收珠子")
      (footprint "jieshou1206")
      (description "PD15-21B/TR8")
      (fields (field (name "PUBLISHER") "Altium Limited"))
      (libsource (lib "Miscellaneous Devices") (part "PD15-21B/TR8"))
    )
    (comp (ref "D41")
      (value "红外接收珠子")
      (footprint "jieshou1206")
      (description "PD15-21B/TR8")
      (fields (field (name "PUBLISHER") "Altium Limited"))
      (libsource (lib "Miscellaneous Devices") (part "PD15-21B/TR8"))
    )
    (comp (ref "D42")
      (value "红外接收珠子")
      (footprint "jieshou1206")
      (description "PD15-21B/TR8")
      (fields (field (name "PUBLISHER") "Altium Limited"))
      (libsource (lib "Miscellaneous Devices") (part "PD15-21B/TR8"))
    )
    (comp (ref "D43")
      (value "红外接收珠子")
      (footprint "jieshou1206")
      (description "PD15-21B/TR8")
      (fields (field (name "PUBLISHER") "Altium Limited"))
      (libsource (lib "Miscellaneous Devices") (part "PD15-21B/TR8"))
    )
    (comp (ref "D44")
      (value "红外接收珠子")
      (footprint "jieshou1206")
      (description "PD15-21B/TR8")
      (fields (field (name "PUBLISHER") "Altium Limited"))
      (libsource (lib "Miscellaneous Devices") (part "PD15-21B/TR8"))
    )
    (comp (ref "D45")
      (value "红外接收珠子")
      (footprint "jieshou1206")
      (description "PD15-21B/TR8")
      (fields (field (name "PUBLISHER") "Altium Limited"))
      (libsource (lib "Miscellaneous Devices") (part "PD15-21B/TR8"))
    )
    (comp (ref "D46")
      (value "红外接收珠子")
      (footprint "jieshou1206")
      (description "PD15-21B/TR8")
      (fields (field (name "PUBLISHER") "Altium Limited"))
      (libsource (lib "Miscellaneous Devices") (part "PD15-21B/TR8"))
    )
    (comp (ref "D47")
      (value "红外接收珠子")
      (footprint "jieshou1206")
      (description "PD15-21B/TR8")
      (fields (field (name "PUBLISHER") "Altium Limited"))
      (libsource (lib "Miscellaneous Devices") (part "PD15-21B/TR8"))
    )
    (comp (ref "D48")
      (value "红外接收珠子")
      (footprint "jieshou1206")
      (description "PD15-21B/TR8")
      (fields (field (name "PUBLISHER") "Altium Limited"))
      (libsource (lib "Miscellaneous Devices") (part "PD15-21B/TR8"))
    )
    (comp (ref "D49")
      (value "红外接收珠子")
      (footprint "jieshou1206")
      (description "PD15-21B/TR8")
      (fields (field (name "PUBLISHER") "Altium Limited"))
      (libsource (lib "Miscellaneous Devices") (part "PD15-21B/TR8"))
    )
    (comp (ref "D50")
      (value "红外接收珠子")
      (footprint "jieshou1206")
      (description "PD15-21B/TR8")
      (fields (field (name "PUBLISHER") "Altium Limited"))
      (libsource (lib "Miscellaneous Devices") (part "PD15-21B/TR8"))
    )
    (comp (ref "D51")
      (value "红外接收珠子")
      (footprint "jieshou1206")
      (description "PD15-21B/TR8")
      (fields (field (name "PUBLISHER") "Altium Limited"))
      (libsource (lib "Miscellaneous Devices") (part "PD15-21B/TR8"))
    )
    (comp (ref "D52")
      (value "红外接收珠子")
      (footprint "jieshou1206")
      (description "PD15-21B/TR8")
      (fields (field (name "PUBLISHER") "Altium Limited"))
      (libsource (lib "Miscellaneous Devices") (part "PD15-21B/TR8"))
    )
    (comp (ref "D53")
      (value "红外接收珠子")
      (footprint "jieshou1206")
      (description "PD15-21B/TR8")
      (fields (field (name "PUBLISHER") "Altium Limited"))
      (libsource (lib "Miscellaneous Devices") (part "PD15-21B/TR8"))
    )
    (comp (ref "D54")
      (value "红外接收珠子")
      (footprint "jieshou1206")
      (description "PD15-21B/TR8")
      (fields (field (name "PUBLISHER") "Altium Limited"))
      (libsource (lib "Miscellaneous Devices") (part "PD15-21B/TR8"))
    )
    (comp (ref "D55")
      (value "红外接收珠子")
      (footprint "jieshou1206")
      (description "PD15-21B/TR8")
      (fields (field (name "PUBLISHER") "Altium Limited"))
      (libsource (lib "Miscellaneous Devices") (part "PD15-21B/TR8"))
    )
    (comp (ref "D56")
      (value "红外接收珠子")
      (footprint "jieshou1206")
      (description "PD15-21B/TR8")
      (fields (field (name "PUBLISHER") "Altium Limited"))
      (libsource (lib "Miscellaneous Devices") (part "PD15-21B/TR8"))
    )
    (comp (ref "D57")
      (value "红外接收珠子")
      (footprint "jieshou1206")
      (description "PD15-21B/TR8")
      (fields (field (name "PUBLISHER") "Altium Limited"))
      (libsource (lib "Miscellaneous Devices") (part "PD15-21B/TR8"))
    )
    (comp (ref "D58")
      (value "红外接收珠子")
      (footprint "jieshou1206")
      (description "PD15-21B/TR8")
      (fields (field (name "PUBLISHER") "Altium Limited"))
      (libsource (lib "Miscellaneous Devices") (part "PD15-21B/TR8"))
    )
    (comp (ref "D59")
      (value "红外接收珠子")
      (footprint "jieshou1206")
      (description "PD15-21B/TR8")
      (fields (field (name "PUBLISHER") "Altium Limited"))
      (libsource (lib "Miscellaneous Devices") (part "PD15-21B/TR8"))
    )
    (comp (ref "D60")
      (value "红外接收珠子")
      (footprint "jieshou1206")
      (description "PD15-21B/TR8")
      (fields (field (name "PUBLISHER") "Altium Limited"))
      (libsource (lib "Miscellaneous Devices") (part "PD15-21B/TR8"))
    )
    (comp (ref "D61")
      (value "红外接收珠子")
      (footprint "jieshou1206")
      (description "PD15-21B/TR8")
      (fields (field (name "PUBLISHER") "Altium Limited"))
      (libsource (lib "Miscellaneous Devices") (part "PD15-21B/TR8"))
    )
    (comp (ref "D62")
      (value "红外接收珠子")
      (footprint "jieshou1206")
      (description "PD15-21B/TR8")
      (fields (field (name "PUBLISHER") "Altium Limited"))
      (libsource (lib "Miscellaneous Devices") (part "PD15-21B/TR8"))
    )
    (comp (ref "D63")
      (value "红外接收珠子")
      (footprint "jieshou1206")
      (description "PD15-21B/TR8")
      (fields (field (name "PUBLISHER") "Altium Limited"))
      (libsource (lib "Miscellaneous Devices") (part "PD15-21B/TR8"))
    )
    (comp (ref "D64")
      (value "红外接收珠子")
      (footprint "jieshou1206")
      (description "PD15-21B/TR8")
      (fields (field (name "PUBLISHER") "Altium Limited"))
      (libsource (lib "Miscellaneous Devices") (part "PD15-21B/TR8"))
    )
    (comp (ref "D65")
      (value "红外接收珠子")
      (footprint "jieshou1206")
      (description "PD15-21B/TR8")
      (fields (field (name "PUBLISHER") "Altium Limited"))
      (libsource (lib "Miscellaneous Devices") (part "PD15-21B/TR8"))
    )
    (comp (ref "D66")
      (value "红外接收珠子")
      (footprint "jieshou1206")
      (description "PD15-21B/TR8")
      (fields (field (name "PUBLISHER") "Altium Limited"))
      (libsource (lib "Miscellaneous Devices") (part "PD15-21B/TR8"))
    )
    (comp (ref "D67")
      (value "红外接收珠子")
      (footprint "jieshou1206")
      (description "PD15-21B/TR8")
      (fields (field (name "PUBLISHER") "Altium Limited"))
      (libsource (lib "Miscellaneous Devices") (part "PD15-21B/TR8"))
    )
    (comp (ref "D68")
      (value "红外接收珠子")
      (footprint "jieshou1206")
      (description "PD15-21B/TR8")
      (fields (field (name "PUBLISHER") "Altium Limited"))
      (libsource (lib "Miscellaneous Devices") (part "PD15-21B/TR8"))
    )
    (comp (ref "D69")
      (value "红外接收珠子")
      (footprint "jieshou1206")
      (description "PD15-21B/TR8")
      (fields (field (name "PUBLISHER") "Altium Limited"))
      (libsource (lib "Miscellaneous Devices") (part "PD15-21B/TR8"))
    )
    (comp (ref "D70")
      (value "红外接收珠子")
      (footprint "jieshou1206")
      (description "PD15-21B/TR8")
      (fields (field (name "PUBLISHER") "Altium Limited"))
      (libsource (lib "Miscellaneous Devices") (part "PD15-21B/TR8"))
    )
    (comp (ref "D71")
      (value "红外接收珠子")
      (footprint "jieshou1206")
      (description "PD15-21B/TR8")
      (fields (field (name "PUBLISHER") "Altium Limited"))
      (libsource (lib "Miscellaneous Devices") (part "PD15-21B/TR8"))
    )
    (comp (ref "D72")
      (value "红外接收珠子")
      (footprint "jieshou1206")
      (description "PD15-21B/TR8")
      (fields (field (name "PUBLISHER") "Altium Limited"))
      (libsource (lib "Miscellaneous Devices") (part "PD15-21B/TR8"))
    )
    (comp (ref "D73")
      (value "红外接收珠子")
      (footprint "jieshou1206")
      (description "PD15-21B/TR8")
      (fields (field (name "PUBLISHER") "Altium Limited"))
      (libsource (lib "Miscellaneous Devices") (part "PD15-21B/TR8"))
    )
    (comp (ref "D74")
      (value "红外接收珠子")
      (footprint "jieshou1206")
      (description "PD15-21B/TR8")
      (fields (field (name "PUBLISHER") "Altium Limited"))
      (libsource (lib "Miscellaneous Devices") (part "PD15-21B/TR8"))
    )
    (comp (ref "D75")
      (value "红外接收珠子")
      (footprint "jieshou1206")
      (description "PD15-21B/TR8")
      (fields (field (name "PUBLISHER") "Altium Limited"))
      (libsource (lib "Miscellaneous Devices") (part "PD15-21B/TR8"))
    )
    (comp (ref "D76")
      (value "红外接收珠子")
      (footprint "jieshou1206")
      (description "PD15-21B/TR8")
      (fields (field (name "PUBLISHER") "Altium Limited"))
      (libsource (lib "Miscellaneous Devices") (part "PD15-21B/TR8"))
    )
    (comp (ref "D77")
      (value "红外接收珠子")
      (footprint "jieshou1206")
      (description "PD15-21B/TR8")
      (fields (field (name "PUBLISHER") "Altium Limited"))
      (libsource (lib "Miscellaneous Devices") (part "PD15-21B/TR8"))
    )
    (comp (ref "D78")
      (value "红外接收珠子")
      (footprint "jieshou1206")
      (description "PD15-21B/TR8")
      (fields (field (name "PUBLISHER") "Altium Limited"))
      (libsource (lib "Miscellaneous Devices") (part "PD15-21B/TR8"))
    )
    (comp (ref "D79")
      (value "红外接收珠子")
      (footprint "jieshou1206")
      (description "PD15-21B/TR8")
      (fields (field (name "PUBLISHER") "Altium Limited"))
      (libsource (lib "Miscellaneous Devices") (part "PD15-21B/TR8"))
    )
    (comp (ref "D80")
      (value "红外接收珠子")
      (footprint "jieshou1206")
      (description "PD15-21B/TR8")
      (fields (field (name "PUBLISHER") "Altium Limited"))
      (libsource (lib "Miscellaneous Devices") (part "PD15-21B/TR8"))
    )
    (comp (ref "D81")
      (value "红外接收珠子")
      (footprint "jieshou1206")
      (description "PD15-21B/TR8")
      (fields (field (name "PUBLISHER") "Altium Limited"))
      (libsource (lib "Miscellaneous Devices") (part "PD15-21B/TR8"))
    )
    (comp (ref "D82")
      (value "红外接收珠子")
      (footprint "jieshou1206")
      (description "PD15-21B/TR8")
      (fields (field (name "PUBLISHER") "Altium Limited"))
      (libsource (lib "Miscellaneous Devices") (part "PD15-21B/TR8"))
    )
    (comp (ref "D83")
      (value "红外接收珠子")
      (footprint "jieshou1206")
      (description "PD15-21B/TR8")
      (fields (field (name "PUBLISHER") "Altium Limited"))
      (libsource (lib "Miscellaneous Devices") (part "PD15-21B/TR8"))
    )
    (comp (ref "D84")
      (value "红外接收珠子")
      (footprint "jieshou1206")
      (description "PD15-21B/TR8")
      (fields (field (name "PUBLISHER") "Altium Limited"))
      (libsource (lib "Miscellaneous Devices") (part "PD15-21B/TR8"))
    )
    (comp (ref "D85")
      (value "红外接收珠子")
      (footprint "jieshou1206")
      (description "PD15-21B/TR8")
      (fields (field (name "PUBLISHER") "Altium Limited"))
      (libsource (lib "Miscellaneous Devices") (part "PD15-21B/TR8"))
    )
    (comp (ref "D86")
      (value "红外接收珠子")
      (footprint "jieshou1206")
      (description "PD15-21B/TR8")
      (fields (field (name "PUBLISHER") "Altium Limited"))
      (libsource (lib "Miscellaneous Devices") (part "PD15-21B/TR8"))
    )
    (comp (ref "D87")
      (value "红外接收珠子")
      (footprint "jieshou1206")
      (description "PD15-21B/TR8")
      (fields (field (name "PUBLISHER") "Altium Limited"))
      (libsource (lib "Miscellaneous Devices") (part "PD15-21B/TR8"))
    )
    (comp (ref "D88")
      (value "红外接收珠子")
      (footprint "jieshou1206")
      (description "PD15-21B/TR8")
      (fields (field (name "PUBLISHER") "Altium Limited"))
      (libsource (lib "Miscellaneous Devices") (part "PD15-21B/TR8"))
    )
    (comp (ref "D89")
      (value "红外接收珠子")
      (footprint "jieshou1206")
      (description "PD15-21B/TR8")
      (fields (field (name "PUBLISHER") "Altium Limited"))
      (libsource (lib "Miscellaneous Devices") (part "PD15-21B/TR8"))
    )
    (comp (ref "D90")
      (value "红外接收珠子")
      (footprint "jieshou1206")
      (description "PD15-21B/TR8")
      (fields (field (name "PUBLISHER") "Altium Limited"))
      (libsource (lib "Miscellaneous Devices") (part "PD15-21B/TR8"))
    )
    (comp (ref "D91")
      (value "红外接收珠子")
      (footprint "jieshou1206")
      (description "PD15-21B/TR8")
      (fields (field (name "PUBLISHER") "Altium Limited"))
      (libsource (lib "Miscellaneous Devices") (part "PD15-21B/TR8"))
    )
    (comp (ref "D92")
      (value "红外接收珠子")
      (footprint "jieshou1206")
      (description "PD15-21B/TR8")
      (fields (field (name "PUBLISHER") "Altium Limited"))
      (libsource (lib "Miscellaneous Devices") (part "PD15-21B/TR8"))
    )
    (comp (ref "D93")
      (value "红外接收珠子")
      (footprint "jieshou1206")
      (description "PD15-21B/TR8")
      (fields (field (name "PUBLISHER") "Altium Limited"))
      (libsource (lib "Miscellaneous Devices") (part "PD15-21B/TR8"))
    )
    (comp (ref "D94")
      (value "红外接收珠子")
      (footprint "jieshou1206")
      (description "PD15-21B/TR8")
      (fields (field (name "PUBLISHER") "Altium Limited"))
      (libsource (lib "Miscellaneous Devices") (part "PD15-21B/TR8"))
    )
    (comp (ref "D95")
      (value "红外接收珠子")
      (footprint "jieshou1206")
      (description "PD15-21B/TR8")
      (fields (field (name "PUBLISHER") "Altium Limited"))
      (libsource (lib "Miscellaneous Devices") (part "PD15-21B/TR8"))
    )
    (comp (ref "D96")
      (value "红外接收珠子")
      (footprint "jieshou1206")
      (description "PD15-21B/TR8")
      (fields (field (name "PUBLISHER") "Altium Limited"))
      (libsource (lib "Miscellaneous Devices") (part "PD15-21B/TR8"))
    )
    (comp (ref "P1")
      (value "牛角插座")
      (footprint "HDR2X12")
      (description "Header, 12-Pin, Dual row")
      (fields (field (name "PUBLISHER") "Altium Limited"))
      (libsource (lib "Miscellaneous Connectors") (part "Header 12X2"))
    )
    (comp (ref "R1")
      (value "4.7K")
      (footprint "0805r")
      (description "电阻")
      (fields (field (name "Comment") "贴片电阻") (field (name "PUBLISHER") "Altium Limited"))
      (libsource (lib "Miscellaneous Devices") (part "Res3"))
    )
    (comp (ref "R2")
      (value "4.7K")
      (footprint "0805r")
      (description "电阻")
      (fields (field (name "Comment") "贴片电阻") (field (name "PUBLISHER") "Altium Limited"))
      (libsource (lib "Miscellaneous Devices") (part "Res3"))
    )
    (comp (ref "R3")
      (value "4.7K")
      (footprint "0805r")
      (description "电阻")
      (fields (field (name "Comment") "贴片电阻") (field (name "PUBLISHER") "Altium Limited"))
      (libsource (lib "Miscellaneous Devices") (part "Res3"))
    )
    (comp (ref "R4")
      (value "4.7K")
      (footprint "0805r")
      (description "电阻")
      (fields (field (name "Comment") "贴片电阻") (field (name "PUBLISHER") "Altium Limited"))
      (libsource (lib "Miscellaneous Devices") (part "Res3"))
    )
    (comp (ref "R5")
      (value "4.7K")
      (footprint "0805r")
      (description "电阻")
      (fields (field (name "Comment") "贴片电阻") (field (name "PUBLISHER") "Altium Limited"))
      (libsource (lib "Miscellaneous Devices") (part "Res3"))
    )
    (comp (ref "R6")
      (value "4.7K")
      (footprint "0805r")
      (description "电阻")
      (fields (field (name "Comment") "贴片电阻") (field (name "PUBLISHER") "Altium Limited"))
      (libsource (lib "Miscellaneous Devices") (part "Res3"))
    )
    (comp (ref "R7")
      (value "4.7K")
      (footprint "0805r")
      (description "电阻")
      (fields (field (name "Comment") "贴片电阻") (field (name "PUBLISHER") "Altium Limited"))
      (libsource (lib "Miscellaneous Devices") (part "Res3"))
    )
    (comp (ref "R8")
      (value "4.7K")
      (footprint "0805r")
      (description "电阻")
      (fields (field (name "Comment") "贴片电阻") (field (name "PUBLISHER") "Altium Limited"))
      (libsource (lib "Miscellaneous Devices") (part "Res3"))
    )
    (comp (ref "R9")
      (value "4.7K")
      (footprint "0805r")
      (description "电阻")
      (fields (field (name "Comment") "贴片电阻") (field (name "PUBLISHER") "Altium Limited"))
      (libsource (lib "Miscellaneous Devices") (part "Res3"))
    )
    (comp (ref "R10")
      (value "4.7K")
      (footprint "0805r")
      (description "电阻")
      (fields (field (name "Comment") "贴片电阻") (field (name "PUBLISHER") "Altium Limited"))
      (libsource (lib "Miscellaneous Devices") (part "Res3"))
    )
    (comp (ref "R11")
      (value "4.7K")
      (footprint "0805r")
      (description "电阻")
      (fields (field (name "Comment") "贴片电阻") (field (name "PUBLISHER") "Altium Limited"))
      (libsource (lib "Miscellaneous Devices") (part "Res3"))
    )
    (comp (ref "R12")
      (value "4.7K")
      (footprint "0805r")
      (description "电阻")
      (fields (field (name "Comment") "贴片电阻") (field (name "PUBLISHER") "Altium Limited"))
      (libsource (lib "Miscellaneous Devices") (part "Res3"))
    )
    (comp (ref "R13")
      (value "4.7K")
      (footprint "0805r")
      (description "电阻")
      (fields (field (name "Comment") "贴片电阻") (field (name "PUBLISHER") "Altium Limited"))
      (libsource (lib "Miscellaneous Devices") (part "Res3"))
    )
    (comp (ref "R14")
      (value "4.7K")
      (footprint "0805r")
      (description "电阻")
      (fields (field (name "Comment") "贴片电阻") (field (name "PUBLISHER") "Altium Limited"))
      (libsource (lib "Miscellaneous Devices") (part "Res3"))
    )
    (comp (ref "R15")
      (value "4.7K")
      (footprint "0805r")
      (description "电阻")
      (fields (field (name "Comment") "贴片电阻") (field (name "PUBLISHER") "Altium Limited"))
      (libsource (lib "Miscellaneous Devices") (part "Res3"))
    )
    (comp (ref "R16")
      (value "4.7K")
      (footprint "0805r")
      (description "电阻")
      (fields (field (name "Comment") "贴片电阻") (field (name "PUBLISHER") "Altium Limited"))
      (libsource (lib "Miscellaneous Devices") (part "Res3"))
    )
    (comp (ref "R17")
      (value "4.7K")
      (footprint "0805r")
      (description "电阻")
      (fields (field (name "Comment") "贴片电阻") (field (name "PUBLISHER") "Altium Limited"))
      (libsource (lib "Miscellaneous Devices") (part "Res3"))
    )
    (comp (ref "R18")
      (value "4.7K")
      (footprint "0805r")
      (description "电阻")
      (fields (field (name "Comment") "贴片电阻") (field (name "PUBLISHER") "Altium Limited"))
      (libsource (lib "Miscellaneous Devices") (part "Res3"))
    )
    (comp (ref "R19")
      (value "4.7K")
      (footprint "0805r")
      (description "电阻")
      (fields (field (name "Comment") "贴片电阻") (field (name "PUBLISHER") "Altium Limited"))
      (libsource (lib "Miscellaneous Devices") (part "Res3"))
    )
    (comp (ref "R20")
      (value "4.7K")
      (footprint "0805r")
      (description "电阻")
      (fields (field (name "Comment") "贴片电阻") (field (name "PUBLISHER") "Altium Limited"))
      (libsource (lib "Miscellaneous Devices") (part "Res3"))
    )
    (comp (ref "R21")
      (value "4.7K")
      (footprint "0805r")
      (description "电阻")
      (fields (field (name "Comment") "贴片电阻") (field (name "PUBLISHER") "Altium Limited"))
      (libsource (lib "Miscellaneous Devices") (part "Res3"))
    )
    (comp (ref "R22")
      (value "4.7K")
      (footprint "0805r")
      (description "电阻")
      (fields (field (name "Comment") "贴片电阻") (field (name "PUBLISHER") "Altium Limited"))
      (libsource (lib "Miscellaneous Devices") (part "Res3"))
    )
    (comp (ref "R23")
      (value "4.7K")
      (footprint "0805r")
      (description "电阻")
      (fields (field (name "Comment") "贴片电阻") (field (name "PUBLISHER") "Altium Limited"))
      (libsource (lib "Miscellaneous Devices") (part "Res3"))
    )
    (comp (ref "R24")
      (value "4.7K")
      (footprint "0805r")
      (description "电阻")
      (fields (field (name "Comment") "贴片电阻") (field (name "PUBLISHER") "Altium Limited"))
      (libsource (lib "Miscellaneous Devices") (part "Res3"))
    )
    (comp (ref "R25")
      (value "4.7K")
      (footprint "0805r")
      (description "电阻")
      (fields (field (name "Comment") "贴片电阻") (field (name "PUBLISHER") "Altium Limited"))
      (libsource (lib "Miscellaneous Devices") (part "Res3"))
    )
    (comp (ref "R26")
      (value "4.7K")
      (footprint "0805r")
      (description "电阻")
      (fields (field (name "Comment") "贴片电阻") (field (name "PUBLISHER") "Altium Limited"))
      (libsource (lib "Miscellaneous Devices") (part "Res3"))
    )
    (comp (ref "R27")
      (value "4.7K")
      (footprint "0805r")
      (description "电阻")
      (fields (field (name "Comment") "贴片电阻") (field (name "PUBLISHER") "Altium Limited"))
      (libsource (lib "Miscellaneous Devices") (part "Res3"))
    )
    (comp (ref "R28")
      (value "4.7K")
      (footprint "0805r")
      (description "电阻")
      (fields (field (name "Comment") "贴片电阻") (field (name "PUBLISHER") "Altium Limited"))
      (libsource (lib "Miscellaneous Devices") (part "Res3"))
    )
    (comp (ref "R29")
      (value "4.7K")
      (footprint "0805r")
      (description "电阻")
      (fields (field (name "Comment") "贴片电阻") (field (name "PUBLISHER") "Altium Limited"))
      (libsource (lib "Miscellaneous Devices") (part "Res3"))
    )
    (comp (ref "R30")
      (value "4.7K")
      (footprint "0805r")
      (description "电阻")
      (fields (field (name "Comment") "贴片电阻") (field (name "PUBLISHER") "Altium Limited"))
      (libsource (lib "Miscellaneous Devices") (part "Res3"))
    )
    (comp (ref "R31")
      (value "4.7K")
      (footprint "0805r")
      (description "电阻")
      (fields (field (name "Comment") "贴片电阻") (field (name "PUBLISHER") "Altium Limited"))
      (libsource (lib "Miscellaneous Devices") (part "Res3"))
    )
    (comp (ref "R32")
      (value "4.7K")
      (footprint "0805r")
      (description "电阻")
      (fields (field (name "Comment") "贴片电阻") (field (name "PUBLISHER") "Altium Limited"))
      (libsource (lib "Miscellaneous Devices") (part "Res3"))
    )
    (comp (ref "R33")
      (value "4.7K")
      (footprint "0805r")
      (description "电阻")
      (fields (field (name "Comment") "贴片电阻") (field (name "PUBLISHER") "Altium Limited"))
      (libsource (lib "Miscellaneous Devices") (part "Res3"))
    )
    (comp (ref "R34")
      (value "4.7K")
      (footprint "0805r")
      (description "电阻")
      (fields (field (name "Comment") "贴片电阻") (field (name "PUBLISHER") "Altium Limited"))
      (libsource (lib "Miscellaneous Devices") (part "Res3"))
    )
    (comp (ref "R35")
      (value "4.7K")
      (footprint "0805r")
      (description "电阻")
      (fields (field (name "Comment") "贴片电阻") (field (name "PUBLISHER") "Altium Limited"))
      (libsource (lib "Miscellaneous Devices") (part "Res3"))
    )
    (comp (ref "R36")
      (value "4.7K")
      (footprint "0805r")
      (description "电阻")
      (fields (field (name "Comment") "贴片电阻") (field (name "PUBLISHER") "Altium Limited"))
      (libsource (lib "Miscellaneous Devices") (part "Res3"))
    )
    (comp (ref "R37")
      (value "4.7K")
      (footprint "0805r")
      (description "电阻")
      (fields (field (name "Comment") "贴片电阻") (field (name "PUBLISHER") "Altium Limited"))
      (libsource (lib "Miscellaneous Devices") (part "Res3"))
    )
    (comp (ref "R38")
      (value "4.7K")
      (footprint "0805r")
      (description "电阻")
      (fields (field (name "Comment") "贴片电阻") (field (name "PUBLISHER") "Altium Limited"))
      (libsource (lib "Miscellaneous Devices") (part "Res3"))
    )
    (comp (ref "R39")
      (value "4.7K")
      (footprint "0805r")
      (description "电阻")
      (fields (field (name "Comment") "贴片电阻") (field (name "PUBLISHER") "Altium Limited"))
      (libsource (lib "Miscellaneous Devices") (part "Res3"))
    )
    (comp (ref "R40")
      (value "4.7K")
      (footprint "0805r")
      (description "电阻")
      (fields (field (name "Comment") "贴片电阻") (field (name "PUBLISHER") "Altium Limited"))
      (libsource (lib "Miscellaneous Devices") (part "Res3"))
    )
    (comp (ref "R41")
      (value "4.7K")
      (footprint "0805r")
      (description "电阻")
      (fields (field (name "Comment") "贴片电阻") (field (name "PUBLISHER") "Altium Limited"))
      (libsource (lib "Miscellaneous Devices") (part "Res3"))
    )
    (comp (ref "R42")
      (value "4.7K")
      (footprint "0805r")
      (description "电阻")
      (fields (field (name "Comment") "贴片电阻") (field (name "PUBLISHER") "Altium Limited"))
      (libsource (lib "Miscellaneous Devices") (part "Res3"))
    )
    (comp (ref "R43")
      (value "4.7K")
      (footprint "0805r")
      (description "电阻")
      (fields (field (name "Comment") "贴片电阻") (field (name "PUBLISHER") "Altium Limited"))
      (libsource (lib "Miscellaneous Devices") (part "Res3"))
    )
    (comp (ref "R44")
      (value "4.7K")
      (footprint "0805r")
      (description "电阻")
      (fields (field (name "Comment") "贴片电阻") (field (name "PUBLISHER") "Altium Limited"))
      (libsource (lib "Miscellaneous Devices") (part "Res3"))
    )
    (comp (ref "R45")
      (value "4.7K")
      (footprint "0805r")
      (description "电阻")
      (fields (field (name "Comment") "贴片电阻") (field (name "PUBLISHER") "Altium Limited"))
      (libsource (lib "Miscellaneous Devices") (part "Res3"))
    )
    (comp (ref "R46")
      (value "4.7K")
      (footprint "0805r")
      (description "电阻")
      (fields (field (name "Comment") "贴片电阻") (field (name "PUBLISHER") "Altium Limited"))
      (libsource (lib "Miscellaneous Devices") (part "Res3"))
    )
    (comp (ref "R47")
      (value "4.7K")
      (footprint "0805r")
      (description "电阻")
      (fields (field (name "Comment") "贴片电阻") (field (name "PUBLISHER") "Altium Limited"))
      (libsource (lib "Miscellaneous Devices") (part "Res3"))
    )
    (comp (ref "R48")
      (value "4.7K")
      (footprint "0805r")
      (description "电阻")
      (fields (field (name "Comment") "贴片电阻") (field (name "PUBLISHER") "Altium Limited"))
      (libsource (lib "Miscellaneous Devices") (part "Res3"))
    )
    (comp (ref "R49")
      (value "4.7K")
      (footprint "0805r")
      (description "电阻")
      (fields (field (name "Comment") "贴片电阻") (field (name "PUBLISHER") "Altium Limited"))
      (libsource (lib "Miscellaneous Devices") (part "Res3"))
    )
    (comp (ref "R50")
      (value "4.7K")
      (footprint "0805r")
      (description "电阻")
      (fields (field (name "Comment") "贴片电阻") (field (name "PUBLISHER") "Altium Limited"))
      (libsource (lib "Miscellaneous Devices") (part "Res3"))
    )
    (comp (ref "R51")
      (value "4.7K")
      (footprint "0805r")
      (description "电阻")
      (fields (field (name "Comment") "贴片电阻") (field (name "PUBLISHER") "Altium Limited"))
      (libsource (lib "Miscellaneous Devices") (part "Res3"))
    )
    (comp (ref "R52")
      (value "4.7K")
      (footprint "0805r")
      (description "电阻")
      (fields (field (name "Comment") "贴片电阻") (field (name "PUBLISHER") "Altium Limited"))
      (libsource (lib "Miscellaneous Devices") (part "Res3"))
    )
    (comp (ref "R53")
      (value "4.7K")
      (footprint "0805r")
      (description "电阻")
      (fields (field (name "Comment") "贴片电阻") (field (name "PUBLISHER") "Altium Limited"))
      (libsource (lib "Miscellaneous Devices") (part "Res3"))
    )
    (comp (ref "R54")
      (value "4.7K")
      (footprint "0805r")
      (description "电阻")
      (fields (field (name "Comment") "贴片电阻") (field (name "PUBLISHER") "Altium Limited"))
      (libsource (lib "Miscellaneous Devices") (part "Res3"))
    )
    (comp (ref "R55")
      (value "4.7K")
      (footprint "0805r")
      (description "电阻")
      (fields (field (name "Comment") "贴片电阻") (field (name "PUBLISHER") "Altium Limited"))
      (libsource (lib "Miscellaneous Devices") (part "Res3"))
    )
    (comp (ref "R56")
      (value "4.7K")
      (footprint "0805r")
      (description "电阻")
      (fields (field (name "Comment") "贴片电阻") (field (name "PUBLISHER") "Altium Limited"))
      (libsource (lib "Miscellaneous Devices") (part "Res3"))
    )
    (comp (ref "R57")
      (value "4.7K")
      (footprint "0805r")
      (description "电阻")
      (fields (field (name "Comment") "贴片电阻") (field (name "PUBLISHER") "Altium Limited"))
      (libsource (lib "Miscellaneous Devices") (part "Res3"))
    )
    (comp (ref "R58")
      (value "4.7K")
      (footprint "0805r")
      (description "电阻")
      (fields (field (name "Comment") "贴片电阻") (field (name "PUBLISHER") "Altium Limited"))
      (libsource (lib "Miscellaneous Devices") (part "Res3"))
    )
    (comp (ref "R59")
      (value "4.7K")
      (footprint "0805r")
      (description "电阻")
      (fields (field (name "Comment") "贴片电阻") (field (name "PUBLISHER") "Altium Limited"))
      (libsource (lib "Miscellaneous Devices") (part "Res3"))
    )
    (comp (ref "R60")
      (value "4.7K")
      (footprint "0805r")
      (description "电阻")
      (fields (field (name "Comment") "贴片电阻") (field (name "PUBLISHER") "Altium Limited"))
      (libsource (lib "Miscellaneous Devices") (part "Res3"))
    )
    (comp (ref "R61")
      (value "4.7K")
      (footprint "0805r")
      (description "电阻")
      (fields (field (name "Comment") "贴片电阻") (field (name "PUBLISHER") "Altium Limited"))
      (libsource (lib "Miscellaneous Devices") (part "Res3"))
    )
    (comp (ref "R62")
      (value "4.7K")
      (footprint "0805r")
      (description "电阻")
      (fields (field (name "Comment") "贴片电阻") (field (name "PUBLISHER") "Altium Limited"))
      (libsource (lib "Miscellaneous Devices") (part "Res3"))
    )
    (comp (ref "R63")
      (value "4.7K")
      (footprint "0805r")
      (description "电阻")
      (fields (field (name "Comment") "贴片电阻") (field (name "PUBLISHER") "Altium Limited"))
      (libsource (lib "Miscellaneous Devices") (part "Res3"))
    )
    (comp (ref "R64")
      (value "4.7K")
      (footprint "0805r")
      (description "电阻")
      (fields (field (name "Comment") "贴片电阻") (field (name "PUBLISHER") "Altium Limited"))
      (libsource (lib "Miscellaneous Devices") (part "Res3"))
    )
    (comp (ref "R65")
      (value "4.7K")
      (footprint "0805r")
      (description "电阻")
      (fields (field (name "Comment") "贴片电阻") (field (name "PUBLISHER") "Altium Limited"))
      (libsource (lib "Miscellaneous Devices") (part "Res3"))
    )
    (comp (ref "R66")
      (value "4.7K")
      (footprint "0805r")
      (description "电阻")
      (fields (field (name "Comment") "贴片电阻") (field (name "PUBLISHER") "Altium Limited"))
      (libsource (lib "Miscellaneous Devices") (part "Res3"))
    )
    (comp (ref "R67")
      (value "4.7K")
      (footprint "0805r")
      (description "电阻")
      (fields (field (name "Comment") "贴片电阻") (field (name "PUBLISHER") "Altium Limited"))
      (libsource (lib "Miscellaneous Devices") (part "Res3"))
    )
    (comp (ref "R68")
      (value "4.7K")
      (footprint "0805r")
      (description "电阻")
      (fields (field (name "Comment") "贴片电阻") (field (name "PUBLISHER") "Altium Limited"))
      (libsource (lib "Miscellaneous Devices") (part "Res3"))
    )
    (comp (ref "R69")
      (value "4.7K")
      (footprint "0805r")
      (description "电阻")
      (fields (field (name "Comment") "贴片电阻") (field (name "PUBLISHER") "Altium Limited"))
      (libsource (lib "Miscellaneous Devices") (part "Res3"))
    )
    (comp (ref "R70")
      (value "4.7K")
      (footprint "0805r")
      (description "电阻")
      (fields (field (name "Comment") "贴片电阻") (field (name "PUBLISHER") "Altium Limited"))
      (libsource (lib "Miscellaneous Devices") (part "Res3"))
    )
    (comp (ref "R71")
      (value "4.7K")
      (footprint "0805r")
      (description "电阻")
      (fields (field (name "Comment") "贴片电阻") (field (name "PUBLISHER") "Altium Limited"))
      (libsource (lib "Miscellaneous Devices") (part "Res3"))
    )
    (comp (ref "R72")
      (value "4.7K")
      (footprint "0805r")
      (description "电阻")
      (fields (field (name "Comment") "贴片电阻") (field (name "PUBLISHER") "Altium Limited"))
      (libsource (lib "Miscellaneous Devices") (part "Res3"))
    )
    (comp (ref "R73")
      (value "4.7K")
      (footprint "0805r")
      (description "电阻")
      (fields (field (name "Comment") "贴片电阻") (field (name "PUBLISHER") "Altium Limited"))
      (libsource (lib "Miscellaneous Devices") (part "Res3"))
    )
    (comp (ref "R74")
      (value "4.7K")
      (footprint "0805r")
      (description "电阻")
      (fields (field (name "Comment") "贴片电阻") (field (name "PUBLISHER") "Altium Limited"))
      (libsource (lib "Miscellaneous Devices") (part "Res3"))
    )
    (comp (ref "R75")
      (value "4.7K")
      (footprint "0805r")
      (description "电阻")
      (fields (field (name "Comment") "贴片电阻") (field (name "PUBLISHER") "Altium Limited"))
      (libsource (lib "Miscellaneous Devices") (part "Res3"))
    )
    (comp (ref "R76")
      (value "4.7K")
      (footprint "0805r")
      (description "电阻")
      (fields (field (name "Comment") "贴片电阻") (field (name "PUBLISHER") "Altium Limited"))
      (libsource (lib "Miscellaneous Devices") (part "Res3"))
    )
    (comp (ref "R77")
      (value "4.7K")
      (footprint "0805r")
      (description "电阻")
      (fields (field (name "Comment") "贴片电阻") (field (name "PUBLISHER") "Altium Limited"))
      (libsource (lib "Miscellaneous Devices") (part "Res3"))
    )
    (comp (ref "R78")
      (value "4.7K")
      (footprint "0805r")
      (description "电阻")
      (fields (field (name "Comment") "贴片电阻") (field (name "PUBLISHER") "Altium Limited"))
      (libsource (lib "Miscellaneous Devices") (part "Res3"))
    )
    (comp (ref "R79")
      (value "4.7K")
      (footprint "0805r")
      (description "电阻")
      (fields (field (name "Comment") "贴片电阻") (field (name "PUBLISHER") "Altium Limited"))
      (libsource (lib "Miscellaneous Devices") (part "Res3"))
    )
    (comp (ref "R80")
      (value "4.7K")
      (footprint "0805r")
      (description "电阻")
      (fields (field (name "Comment") "贴片电阻") (field (name "PUBLISHER") "Altium Limited"))
      (libsource (lib "Miscellaneous Devices") (part "Res3"))
    )
    (comp (ref "R81")
      (value "4.7K")
      (footprint "0805r")
      (description "电阻")
      (fields (field (name "Comment") "贴片电阻") (field (name "PUBLISHER") "Altium Limited"))
      (libsource (lib "Miscellaneous Devices") (part "Res3"))
    )
    (comp (ref "R82")
      (value "4.7K")
      (footprint "0805r")
      (description "电阻")
      (fields (field (name "Comment") "贴片电阻") (field (name "PUBLISHER") "Altium Limited"))
      (libsource (lib "Miscellaneous Devices") (part "Res3"))
    )
    (comp (ref "R83")
      (value "4.7K")
      (footprint "0805r")
      (description "电阻")
      (fields (field (name "Comment") "贴片电阻") (field (name "PUBLISHER") "Altium Limited"))
      (libsource (lib "Miscellaneous Devices") (part "Res3"))
    )
    (comp (ref "R84")
      (value "4.7K")
      (footprint "0805r")
      (description "电阻")
      (fields (field (name "Comment") "贴片电阻") (field (name "PUBLISHER") "Altium Limited"))
      (libsource (lib "Miscellaneous Devices") (part "Res3"))
    )
    (comp (ref "R85")
      (value "4.7K")
      (footprint "0805r")
      (description "电阻")
      (fields (field (name "Comment") "贴片电阻") (field (name "PUBLISHER") "Altium Limited"))
      (libsource (lib "Miscellaneous Devices") (part "Res3"))
    )
    (comp (ref "R86")
      (value "4.7K")
      (footprint "0805r")
      (description "电阻")
      (fields (field (name "Comment") "贴片电阻") (field (name "PUBLISHER") "Altium Limited"))
      (libsource (lib "Miscellaneous Devices") (part "Res3"))
    )
    (comp (ref "R87")
      (value "4.7K")
      (footprint "0805r")
      (description "电阻")
      (fields (field (name "Comment") "贴片电阻") (field (name "PUBLISHER") "Altium Limited"))
      (libsource (lib "Miscellaneous Devices") (part "Res3"))
    )
    (comp (ref "R88")
      (value "4.7K")
      (footprint "0805r")
      (description "电阻")
      (fields (field (name "Comment") "贴片电阻") (field (name "PUBLISHER") "Altium Limited"))
      (libsource (lib "Miscellaneous Devices") (part "Res3"))
    )
    (comp (ref "R89")
      (value "4.7K")
      (footprint "0805r")
      (description "电阻")
      (fields (field (name "Comment") "贴片电阻") (field (name "PUBLISHER") "Altium Limited"))
      (libsource (lib "Miscellaneous Devices") (part "Res3"))
    )
    (comp (ref "R90")
      (value "4.7K")
      (footprint "0805r")
      (description "电阻")
      (fields (field (name "Comment") "贴片电阻") (field (name "PUBLISHER") "Altium Limited"))
      (libsource (lib "Miscellaneous Devices") (part "Res3"))
    )
    (comp (ref "R91")
      (value "4.7K")
      (footprint "0805r")
      (description "电阻")
      (fields (field (name "Comment") "贴片电阻") (field (name "PUBLISHER") "Altium Limited"))
      (libsource (lib "Miscellaneous Devices") (part "Res3"))
    )
    (comp (ref "R92")
      (value "4.7K")
      (footprint "0805r")
      (description "电阻")
      (fields (field (name "Comment") "贴片电阻") (field (name "PUBLISHER") "Altium Limited"))
      (libsource (lib "Miscellaneous Devices") (part "Res3"))
    )
    (comp (ref "R93")
      (value "4.7K")
      (footprint "0805r")
      (description "电阻")
      (fields (field (name "Comment") "贴片电阻") (field (name "PUBLISHER") "Altium Limited"))
      (libsource (lib "Miscellaneous Devices") (part "Res3"))
    )
    (comp (ref "R94")
      (value "4.7K")
      (footprint "0805r")
      (description "电阻")
      (fields (field (name "Comment") "贴片电阻") (field (name "PUBLISHER") "Altium Limited"))
      (libsource (lib "Miscellaneous Devices") (part "Res3"))
    )
    (comp (ref "R95")
      (value "4.7K")
      (footprint "0805r")
      (description "电阻")
      (fields (field (name "Comment") "贴片电阻") (field (name "PUBLISHER") "Altium Limited"))
      (libsource (lib "Miscellaneous Devices") (part "Res3"))
    )
    (comp (ref "R96")
      (value "4.7K")
      (footprint "0805r")
      (description "电阻")
      (fields (field (name "Comment") "贴片电阻") (field (name "PUBLISHER") "Altium Limited"))
      (libsource (lib "Miscellaneous Devices") (part "Res3"))
    )
    (comp (ref "U1")
      (value "集成电路")
      (footprint "TSSOP16")
      (description "ADG708BRU-REEL")
      (libsource (lib "MYlib") (part "ADG708"))
    )
    (comp (ref "U2")
      (value "集成电路")
      (footprint "TSSOP16")
      (description "ADG708BRU-REEL")
      (libsource (lib "MYlib") (part "ADG708"))
    )
    (comp (ref "U3")
      (value "集成电路")
      (footprint "TSSOP16")
      (description "ADG708BRU-REEL")
      (libsource (lib "MYlib") (part "ADG708"))
    )
    (comp (ref "U4")
      (value "集成电路")
      (footprint "TSSOP16")
      (description "ADG708BRU-REEL")
      (libsource (lib "MYlib") (part "ADG708"))
    )
    (comp (ref "U5")
      (value "集成电路")
      (footprint "TSSOP16")
      (description "ADG708BRU-REEL")
      (libsource (lib "MYlib") (part "ADG708"))
    )
    (comp (ref "U6")
      (value "集成电路")
      (footprint "TSSOP16")
      (description "ADG708BRU-REEL")
      (libsource (lib "MYlib") (part "ADG708"))
    )
    (comp (ref "U7")
      (value "集成电路")
      (footprint "TSSOP16")
      (description "ADG708BRU-REEL")
      (libsource (lib "MYlib") (part "ADG708"))
    )
    (comp (ref "U8")
      (value "集成电路")
      (footprint "TSSOP16")
      (description "ADG708BRU-REEL")
      (libsource (lib "MYlib") (part "ADG708"))
    )
    (comp (ref "U9")
      (value "集成电路")
      (footprint "TSSOP16")
      (description "ADG708BRU-REEL")
      (libsource (lib "MYlib") (part "ADG708"))
    )
    (comp (ref "U10")
      (value "集成电路")
      (footprint "TSSOP16")
      (description "ADG708BRU-REEL")
      (libsource (lib "MYlib") (part "ADG708"))
    )
    (comp (ref "U11")
      (value "集成电路")
      (footprint "TSSOP16")
      (description "ADG708BRU-REEL")
      (libsource (lib "MYlib") (part "ADG708"))
    )
    (comp (ref "U12")
      (value "集成电路")
      (footprint "TSSOP16")
      (description "ADG708BRU-REEL")
      (libsource (lib "MYlib") (part "ADG708"))
    )
  )
  (nets
    (net (code "1") (name "/A0") (class "Default")
      (node (ref "P1") (pin "1") (pinfunction "1_1") (pintype "passive"))
      (node (ref "U1") (pin "1") (pinfunction "A0_1") (pintype "passive"))
      (node (ref "U10") (pin "1") (pinfunction "A0_1") (pintype "passive"))
      (node (ref "U11") (pin "1") (pinfunction "A0_1") (pintype "passive"))
      (node (ref "U12") (pin "1") (pinfunction "A0_1") (pintype "passive"))
      (node (ref "U2") (pin "1") (pinfunction "A0_1") (pintype "passive"))
      (node (ref "U3") (pin "1") (pinfunction "A0_1") (pintype "passive"))
      (node (ref "U4") (pin "1") (pinfunction "A0_1") (pintype "passive"))
      (node (ref "U5") (pin "1") (pinfunction "A0_1") (pintype "passive"))
      (node (ref "U6") (pin "1") (pinfunction "A0_1") (pintype "passive"))
      (node (ref "U7") (pin "1") (pinfunction "A0_1") (pintype "passive"))
      (node (ref "U8") (pin "1") (pinfunction "A0_1") (pintype "passive"))
      (node (ref "U9") (pin "1") (pinfunction "A0_1") (pintype "passive"))
    )
    (net (code "2") (name "/A1") (class "Default")
      (node (ref "P1") (pin "3") (pinfunction "3_3") (pintype "passive"))
      (node (ref "U1") (pin "16") (pinfunction "A1_16") (pintype "passive"))
      (node (ref "U10") (pin "16") (pinfunction "A1_16") (pintype "passive"))
      (node (ref "U11") (pin "16") (pinfunction "A1_16") (pintype "passive"))
      (node (ref "U12") (pin "16") (pinfunction "A1_16") (pintype "passive"))
      (node (ref "U2") (pin "16") (pinfunction "A1_16") (pintype "passive"))
      (node (ref "U3") (pin "16") (pinfunction "A1_16") (pintype "passive"))
      (node (ref "U4") (pin "16") (pinfunction "A1_16") (pintype "passive"))
      (node (ref "U5") (pin "16") (pinfunction "A1_16") (pintype "passive"))
      (node (ref "U6") (pin "16") (pinfunction "A1_16") (pintype "passive"))
      (node (ref "U7") (pin "16") (pinfunction "A1_16") (pintype "passive"))
      (node (ref "U8") (pin "16") (pinfunction "A1_16") (pintype "passive"))
      (node (ref "U9") (pin "16") (pinfunction "A1_16") (pintype "passive"))
    )
    (net (code "3") (name "/A2") (class "Default")
      (node (ref "P1") (pin "5") (pinfunction "5_5") (pintype "passive"))
      (node (ref "U1") (pin "15") (pinfunction "A2_15") (pintype "passive"))
      (node (ref "U10") (pin "15") (pinfunction "A2_15") (pintype "passive"))
      (node (ref "U11") (pin "15") (pinfunction "A2_15") (pintype "passive"))
      (node (ref "U12") (pin "15") (pinfunction "A2_15") (pintype "passive"))
      (node (ref "U2") (pin "15") (pinfunction "A2_15") (pintype "passive"))
      (node (ref "U3") (pin "15") (pinfunction "A2_15") (pintype "passive"))
      (node (ref "U4") (pin "15") (pinfunction "A2_15") (pintype "passive"))
      (node (ref "U5") (pin "15") (pinfunction "A2_15") (pintype "passive"))
      (node (ref "U6") (pin "15") (pinfunction "A2_15") (pintype "passive"))
      (node (ref "U7") (pin "15") (pinfunction "A2_15") (pintype "passive"))
      (node (ref "U8") (pin "15") (pinfunction "A2_15") (pintype "passive"))
      (node (ref "U9") (pin "15") (pinfunction "A2_15") (pintype "passive"))
    )
    (net (code "4") (name "/CH1") (class "Default")
      (node (ref "P1") (pin "2") (pinfunction "2_2") (pintype "passive"))
      (node (ref "U1") (pin "8") (pinfunction "D_8") (pintype "passive"))
    )
    (net (code "5") (name "/CH1-1") (class "Default")
      (node (ref "C5") (pin "2") (pinfunction "2_2") (pintype "passive"))
      (node (ref "D1") (pin "1") (pinfunction "A_1") (pintype "passive"))
      (node (ref "R1") (pin "2") (pinfunction "2_2") (pintype "passive"))
      (node (ref "U1") (pin "4") (pinfunction "S1_4") (pintype "passive"))
    )
    (net (code "6") (name "/CH1-2") (class "Default")
      (node (ref "C6") (pin "2") (pinfunction "2_2") (pintype "passive"))
      (node (ref "D2") (pin "1") (pinfunction "A_1") (pintype "passive"))
      (node (ref "R2") (pin "2") (pinfunction "2_2") (pintype "passive"))
      (node (ref "U1") (pin "5") (pinfunction "S2_5") (pintype "passive"))
    )
    (net (code "7") (name "/CH1-3") (class "Default")
      (node (ref "C7") (pin "2") (pinfunction "2_2") (pintype "passive"))
      (node (ref "D3") (pin "1") (pinfunction "A_1") (pintype "passive"))
      (node (ref "R3") (pin "2") (pinfunction "2_2") (pintype "passive"))
      (node (ref "U1") (pin "6") (pinfunction "S3_6") (pintype "passive"))
    )
    (net (code "8") (name "/CH1-4") (class "Default")
      (node (ref "C8") (pin "2") (pinfunction "2_2") (pintype "passive"))
      (node (ref "D4") (pin "1") (pinfunction "A_1") (pintype "passive"))
      (node (ref "R4") (pin "2") (pinfunction "2_2") (pintype "passive"))
      (node (ref "U1") (pin "7") (pinfunction "S4_7") (pintype "passive"))
    )
    (net (code "9") (name "/CH1-5") (class "Default")
      (node (ref "C9") (pin "2") (pinfunction "2_2") (pintype "passive"))
      (node (ref "D5") (pin "1") (pinfunction "A_1") (pintype "passive"))
      (node (ref "R5") (pin "2") (pinfunction "2_2") (pintype "passive"))
      (node (ref "U1") (pin "12") (pinfunction "S5_12") (pintype "passive"))
    )
    (net (code "10") (name "/CH1-6") (class "Default")
      (node (ref "C10") (pin "2") (pinfunction "2_2") (pintype "passive"))
      (node (ref "D6") (pin "1") (pinfunction "A_1") (pintype "passive"))
      (node (ref "R6") (pin "2") (pinfunction "2_2") (pintype "passive"))
      (node (ref "U1") (pin "11") (pinfunction "S6_11") (pintype "passive"))
    )
    (net (code "11") (name "/CH1-7") (class "Default")
      (node (ref "C11") (pin "2") (pinfunction "2_2") (pintype "passive"))
      (node (ref "D7") (pin "1") (pinfunction "A_1") (pintype "passive"))
      (node (ref "R7") (pin "2") (pinfunction "2_2") (pintype "passive"))
      (node (ref "U1") (pin "10") (pinfunction "S7_10") (pintype "passive"))
    )
    (net (code "12") (name "/CH1-8") (class "Default")
      (node (ref "C12") (pin "2") (pinfunction "2_2") (pintype "passive"))
      (node (ref "D8") (pin "1") (pinfunction "A_1") (pintype "passive"))
      (node (ref "R8") (pin "2") (pinfunction "2_2") (pintype "passive"))
      (node (ref "U1") (pin "9") (pinfunction "S8_9") (pintype "passive"))
    )
    (net (code "13") (name "/CH2") (class "Default")
      (node (ref "P1") (pin "4") (pinfunction "4_4") (pintype "passive"))
      (node (ref "U2") (pin "8") (pinfunction "D_8") (pintype "passive"))
    )
    (net (code "14") (name "/CH2-1") (class "Default")
      (node (ref "C13") (pin "2") (pinfunction "2_2") (pintype "passive"))
      (node (ref "D9") (pin "1") (pinfunction "A_1") (pintype "passive"))
      (node (ref "R9") (pin "2") (pinfunction "2_2") (pintype "passive"))
      (node (ref "U2") (pin "4") (pinfunction "S1_4") (pintype "passive"))
    )
    (net (code "15") (name "/CH2-2") (class "Default")
      (node (ref "C14") (pin "2") (pinfunction "2_2") (pintype "passive"))
      (node (ref "D10") (pin "1") (pinfunction "A_1") (pintype "passive"))
      (node (ref "R10") (pin "2") (pinfunction "2_2") (pintype "passive"))
      (node (ref "U2") (pin "5") (pinfunction "S2_5") (pintype "passive"))
    )
    (net (code "16") (name "/CH2-3") (class "Default")
      (node (ref "C15") (pin "2") (pinfunction "2_2") (pintype "passive"))
      (node (ref "D11") (pin "1") (pinfunction "A_1") (pintype "passive"))
      (node (ref "R11") (pin "2") (pinfunction "2_2") (pintype "passive"))
      (node (ref "U2") (pin "6") (pinfunction "S3_6") (pintype "passive"))
    )
    (net (code "17") (name "/CH2-4") (class "Default")
      (node (ref "C16") (pin "2") (pinfunction "2_2") (pintype "passive"))
      (node (ref "D12") (pin "1") (pinfunction "A_1") (pintype "passive"))
      (node (ref "R12") (pin "2") (pinfunction "2_2") (pintype "passive"))
      (node (ref "U2") (pin "7") (pinfunction "S4_7") (pintype "passive"))
    )
    (net (code "18") (name "/CH2-5") (class "Default")
      (node (ref "C17") (pin "2") (pinfunction "2_2") (pintype "passive"))
      (node (ref "D13") (pin "1") (pinfunction "A_1") (pintype "passive"))
      (node (ref "R13") (pin "2") (pinfunction "2_2") (pintype "passive"))
      (node (ref "U2") (pin "12") (pinfunction "S5_12") (pintype "passive"))
    )
    (net (code "19") (name "/CH2-6") (class "Default")
      (node (ref "C18") (pin "2") (pinfunction "2_2") (pintype "passive"))
      (node (ref "D14") (pin "1") (pinfunction "A_1") (pintype "passive"))
      (node (ref "R14") (pin "2") (pinfunction "2_2") (pintype "passive"))
      (node (ref "U2") (pin "11") (pinfunction "S6_11") (pintype "passive"))
    )
    (net (code "20") (name "/CH2-7") (class "Default")
      (node (ref "C19") (pin "2") (pinfunction "2_2") (pintype "passive"))
      (node (ref "D15") (pin "1") (pinfunction "A_1") (pintype "passive"))
      (node (ref "R15") (pin "2") (pinfunction "2_2") (pintype "passive"))
      (node (ref "U2") (pin "10") (pinfunction "S7_10") (pintype "passive"))
    )
    (net (code "21") (name "/CH2-8") (class "Default")
      (node (ref "C20") (pin "2") (pinfunction "2_2") (pintype "passive"))
      (node (ref "D16") (pin "1") (pinfunction "A_1") (pintype "passive"))
      (node (ref "R16") (pin "2") (pinfunction "2_2") (pintype "passive"))
      (node (ref "U2") (pin "9") (pinfunction "S8_9") (pintype "passive"))
    )
    (net (code "22") (name "/CH3") (class "Default")
      (node (ref "P1") (pin "6") (pinfunction "6_6") (pintype "passive"))
      (node (ref "U3") (pin "8") (pinfunction "D_8") (pintype "passive"))
    )
    (net (code "23") (name "/CH3-1") (class "Default")
      (node (ref "C21") (pin "2") (pinfunction "2_2") (pintype "passive"))
      (node (ref "D17") (pin "1") (pinfunction "A_1") (pintype "passive"))
      (node (ref "R17") (pin "2") (pinfunction "2_2") (pintype "passive"))
      (node (ref "U3") (pin "4") (pinfunction "S1_4") (pintype "passive"))
    )
    (net (code "24") (name "/CH3-2") (class "Default")
      (node (ref "C22") (pin "2") (pinfunction "2_2") (pintype "passive"))
      (node (ref "D18") (pin "1") (pinfunction "A_1") (pintype "passive"))
      (node (ref "R18") (pin "2") (pinfunction "2_2") (pintype "passive"))
      (node (ref "U3") (pin "5") (pinfunction "S2_5") (pintype "passive"))
    )
    (net (code "25") (name "/CH3-3") (class "Default")
      (node (ref "C23") (pin "2") (pinfunction "2_2") (pintype "passive"))
      (node (ref "D19") (pin "1") (pinfunction "A_1") (pintype "passive"))
      (node (ref "R19") (pin "2") (pinfunction "2_2") (pintype "passive"))
      (node (ref "U3") (pin "6") (pinfunction "S3_6") (pintype "passive"))
    )
    (net (code "26") (name "/CH3-4") (class "Default")
      (node (ref "C24") (pin "2") (pinfunction "2_2") (pintype "passive"))
      (node (ref "D20") (pin "1") (pinfunction "A_1") (pintype "passive"))
      (node (ref "R20") (pin "2") (pinfunction "2_2") (pintype "passive"))
      (node (ref "U3") (pin "7") (pinfunction "S4_7") (pintype "passive"))
    )
    (net (code "27") (name "/CH3-5") (class "Default")
      (node (ref "C25") (pin "2") (pinfunction "2_2") (pintype "passive"))
      (node (ref "D21") (pin "1") (pinfunction "A_1") (pintype "passive"))
      (node (ref "R21") (pin "2") (pinfunction "2_2") (pintype "passive"))
      (node (ref "U3") (pin "12") (pinfunction "S5_12") (pintype "passive"))
    )
    (net (code "28") (name "/CH3-6") (class "Default")
      (node (ref "C26") (pin "2") (pinfunction "2_2") (pintype "passive"))
      (node (ref "D22") (pin "1") (pinfunction "A_1") (pintype "passive"))
      (node (ref "R22") (pin "2") (pinfunction "2_2") (pintype "passive"))
      (node (ref "U3") (pin "11") (pinfunction "S6_11") (pintype "passive"))
    )
    (net (code "29") (name "/CH3-7") (class "Default")
      (node (ref "C27") (pin "2") (pinfunction "2_2") (pintype "passive"))
      (node (ref "D23") (pin "1") (pinfunction "A_1") (pintype "passive"))
      (node (ref "R23") (pin "2") (pinfunction "2_2") (pintype "passive"))
      (node (ref "U3") (pin "10") (pinfunction "S7_10") (pintype "passive"))
    )
    (net (code "30") (name "/CH3-8") (class "Default")
      (node (ref "C28") (pin "2") (pinfunction "2_2") (pintype "passive"))
      (node (ref "D24") (pin "1") (pinfunction "A_1") (pintype "passive"))
      (node (ref "R24") (pin "2") (pinfunction "2_2") (pintype "passive"))
      (node (ref "U3") (pin "9") (pinfunction "S8_9") (pintype "passive"))
    )
    (net (code "31") (name "/CH4") (class "Default")
      (node (ref "P1") (pin "8") (pinfunction "8_8") (pintype "passive"))
      (node (ref "U4") (pin "8") (pinfunction "D_8") (pintype "passive"))
    )
    (net (code "32") (name "/CH4-1") (class "Default")
      (node (ref "C29") (pin "2") (pinfunction "2_2") (pintype "passive"))
      (node (ref "D25") (pin "1") (pinfunction "A_1") (pintype "passive"))
      (node (ref "R25") (pin "2") (pinfunction "2_2") (pintype "passive"))
      (node (ref "U4") (pin "4") (pinfunction "S1_4") (pintype "passive"))
    )
    (net (code "33") (name "/CH4-2") (class "Default")
      (node (ref "C30") (pin "2") (pinfunction "2_2") (pintype "passive"))
      (node (ref "D26") (pin "1") (pinfunction "A_1") (pintype "passive"))
      (node (ref "R26") (pin "2") (pinfunction "2_2") (pintype "passive"))
      (node (ref "U4") (pin "5") (pinfunction "S2_5") (pintype "passive"))
    )
    (net (code "34") (name "/CH4-3") (class "Default")
      (node (ref "C31") (pin "2") (pinfunction "2_2") (pintype "passive"))
      (node (ref "D27") (pin "1") (pinfunction "A_1") (pintype "passive"))
      (node (ref "R27") (pin "2") (pinfunction "2_2") (pintype "passive"))
      (node (ref "U4") (pin "6") (pinfunction "S3_6") (pintype "passive"))
    )
    (net (code "35") (name "/CH4-4") (class "Default")
      (node (ref "C32") (pin "2") (pinfunction "2_2") (pintype "passive"))
      (node (ref "D28") (pin "1") (pinfunction "A_1") (pintype "passive"))
      (node (ref "R28") (pin "2") (pinfunction "2_2") (pintype "passive"))
      (node (ref "U4") (pin "7") (pinfunction "S4_7") (pintype "passive"))
    )
    (net (code "36") (name "/CH4-5") (class "Default")
      (node (ref "C33") (pin "2") (pinfunction "2_2") (pintype "passive"))
      (node (ref "D29") (pin "1") (pinfunction "A_1") (pintype "passive"))
      (node (ref "R29") (pin "2") (pinfunction "2_2") (pintype "passive"))
      (node (ref "U4") (pin "12") (pinfunction "S5_12") (pintype "passive"))
    )
    (net (code "37") (name "/CH4-6") (class "Default")
      (node (ref "C34") (pin "2") (pinfunction "2_2") (pintype "passive"))
      (node (ref "D30") (pin "1") (pinfunction "A_1") (pintype "passive"))
      (node (ref "R30") (pin "2") (pinfunction "2_2") (pintype "passive"))
      (node (ref "U4") (pin "11") (pinfunction "S6_11") (pintype "passive"))
    )
    (net (code "38") (name "/CH4-7") (class "Default")
      (node (ref "C35") (pin "2") (pinfunction "2_2") (pintype "passive"))
      (node (ref "D31") (pin "1") (pinfunction "A_1") (pintype "passive"))
      (node (ref "R31") (pin "2") (pinfunction "2_2") (pintype "passive"))
      (node (ref "U4") (pin "10") (pinfunction "S7_10") (pintype "passive"))
    )
    (net (code "39") (name "/CH4-8") (class "Default")
      (node (ref "C36") (pin "2") (pinfunction "2_2") (pintype "passive"))
      (node (ref "D32") (pin "1") (pinfunction "A_1") (pintype "passive"))
      (node (ref "R32") (pin "2") (pinfunction "2_2") (pintype "passive"))
      (node (ref "U4") (pin "9") (pinfunction "S8_9") (pintype "passive"))
    )
    (net (code "40") (name "/CH5") (class "Default")
      (node (ref "P1") (pin "10") (pinfunction "10_10") (pintype "passive"))
      (node (ref "U5") (pin "8") (pinfunction "D_8") (pintype "passive"))
    )
    (net (code "41") (name "/CH5-1") (class "Default")
      (node (ref "C37") (pin "2") (pinfunction "2_2") (pintype "passive"))
      (node (ref "D33") (pin "1") (pinfunction "A_1") (pintype "passive"))
      (node (ref "R33") (pin "2") (pinfunction "2_2") (pintype "passive"))
      (node (ref "U5") (pin "4") (pinfunction "S1_4") (pintype "passive"))
    )
    (net (code "42") (name "/CH5-2") (class "Default")
      (node (ref "C38") (pin "2") (pinfunction "2_2") (pintype "passive"))
      (node (ref "D34") (pin "1") (pinfunction "A_1") (pintype "passive"))
      (node (ref "R34") (pin "2") (pinfunction "2_2") (pintype "passive"))
      (node (ref "U5") (pin "5") (pinfunction "S2_5") (pintype "passive"))
    )
    (net (code "43") (name "/CH5-3") (class "Default")
      (node (ref "C39") (pin "2") (pinfunction "2_2") (pintype "passive"))
      (node (ref "D35") (pin "1") (pinfunction "A_1") (pintype "passive"))
      (node (ref "R35") (pin "2") (pinfunction "2_2") (pintype "passive"))
      (node (ref "U5") (pin "6") (pinfunction "S3_6") (pintype "passive"))
    )
    (net (code "44") (name "/CH5-4") (class "Default")
      (node (ref "C40") (pin "2") (pinfunction "2_2") (pintype "passive"))
      (node (ref "D36") (pin "1") (pinfunction "A_1") (pintype "passive"))
      (node (ref "R36") (pin "2") (pinfunction "2_2") (pintype "passive"))
      (node (ref "U5") (pin "7") (pinfunction "S4_7") (pintype "passive"))
    )
    (net (code "45") (name "/CH5-5") (class "Default")
      (node (ref "C41") (pin "2") (pinfunction "2_2") (pintype "passive"))
      (node (ref "D37") (pin "1") (pinfunction "A_1") (pintype "passive"))
      (node (ref "R37") (pin "2") (pinfunction "2_2") (pintype "passive"))
      (node (ref "U5") (pin "12") (pinfunction "S5_12") (pintype "passive"))
    )
    (net (code "46") (name "/CH5-6") (class "Default")
      (node (ref "C42") (pin "2") (pinfunction "2_2") (pintype "passive"))
      (node (ref "D38") (pin "1") (pinfunction "A_1") (pintype "passive"))
      (node (ref "R38") (pin "2") (pinfunction "2_2") (pintype "passive"))
      (node (ref "U5") (pin "11") (pinfunction "S6_11") (pintype "passive"))
    )
    (net (code "47") (name "/CH5-7") (class "Default")
      (node (ref "C43") (pin "2") (pinfunction "2_2") (pintype "passive"))
      (node (ref "D39") (pin "1") (pinfunction "A_1") (pintype "passive"))
      (node (ref "R39") (pin "2") (pinfunction "2_2") (pintype "passive"))
      (node (ref "U5") (pin "10") (pinfunction "S7_10") (pintype "passive"))
    )
    (net (code "48") (name "/CH5-8") (class "Default")
      (node (ref "C44") (pin "2") (pinfunction "2_2") (pintype "passive"))
      (node (ref "D40") (pin "1") (pinfunction "A_1") (pintype "passive"))
      (node (ref "R40") (pin "2") (pinfunction "2_2") (pintype "passive"))
      (node (ref "U5") (pin "9") (pinfunction "S8_9") (pintype "passive"))
    )
    (net (code "49") (name "/CH6") (class "Default")
      (node (ref "P1") (pin "12") (pinfunction "12_12") (pintype "passive"))
      (node (ref "U6") (pin "8") (pinfunction "D_8") (pintype "passive"))
    )
    (net (code "50") (name "/CH6-1") (class "Default")
      (node (ref "C45") (pin "2") (pinfunction "2_2") (pintype "passive"))
      (node (ref "D41") (pin "1") (pinfunction "A_1") (pintype "passive"))
      (node (ref "R41") (pin "2") (pinfunction "2_2") (pintype "passive"))
      (node (ref "U6") (pin "4") (pinfunction "S1_4") (pintype "passive"))
    )
    (net (code "51") (name "/CH6-2") (class "Default")
      (node (ref "C46") (pin "2") (pinfunction "2_2") (pintype "passive"))
      (node (ref "D42") (pin "1") (pinfunction "A_1") (pintype "passive"))
      (node (ref "R42") (pin "2") (pinfunction "2_2") (pintype "passive"))
      (node (ref "U6") (pin "5") (pinfunction "S2_5") (pintype "passive"))
    )
    (net (code "52") (name "/CH6-3") (class "Default")
      (node (ref "C47") (pin "2") (pinfunction "2_2") (pintype "passive"))
      (node (ref "D43") (pin "1") (pinfunction "A_1") (pintype "passive"))
      (node (ref "R43") (pin "2") (pinfunction "2_2") (pintype "passive"))
      (node (ref "U6") (pin "6") (pinfunction "S3_6") (pintype "passive"))
    )
    (net (code "53") (name "/CH6-4") (class "Default")
      (node (ref "C48") (pin "2") (pinfunction "2_2") (pintype "passive"))
      (node (ref "D44") (pin "1") (pinfunction "A_1") (pintype "passive"))
      (node (ref "R44") (pin "2") (pinfunction "2_2") (pintype "passive"))
      (node (ref "U6") (pin "7") (pinfunction "S4_7") (pintype "passive"))
    )
    (net (code "54") (name "/CH6-5") (class "Default")
      (node (ref "C49") (pin "2") (pinfunction "2_2") (pintype "passive"))
      (node (ref "D45") (pin "1") (pinfunction "A_1") (pintype "passive"))
      (node (ref "R45") (pin "2") (pinfunction "2_2") (pintype "passive"))
      (node (ref "U6") (pin "12") (pinfunction "S5_12") (pintype "passive"))
    )
    (net (code "55") (name "/CH6-6") (class "Default")
      (node (ref "C50") (pin "2") (pinfunction "2_2") (pintype "passive"))
      (node (ref "D46") (pin "1") (pinfunction "A_1") (pintype "passive"))
      (node (ref "R46") (pin "2") (pinfunction "2_2") (pintype "passive"))
      (node (ref "U6") (pin "11") (pinfunction "S6_11") (pintype "passive"))
    )
    (net (code "56") (name "/CH6-7") (class "Default")
      (node (ref "C51") (pin "2") (pinfunction "2_2") (pintype "passive"))
      (node (ref "D47") (pin "1") (pinfunction "A_1") (pintype "passive"))
      (node (ref "R47") (pin "2") (pinfunction "2_2") (pintype "passive"))
      (node (ref "U6") (pin "10") (pinfunction "S7_10") (pintype "passive"))
    )
    (net (code "57") (name "/CH6-8") (class "Default")
      (node (ref "C52") (pin "2") (pinfunction "2_2") (pintype "passive"))
      (node (ref "D48") (pin "1") (pinfunction "A_1") (pintype "passive"))
      (node (ref "R48") (pin "2") (pinfunction "2_2") (pintype "passive"))
      (node (ref "U6") (pin "9") (pinfunction "S8_9") (pintype "passive"))
    )
    (net (code "58") (name "/CH7") (class "Default")
      (node (ref "P1") (pin "14") (pinfunction "14_14") (pintype "passive"))
      (node (ref "U7") (pin "8") (pinfunction "D_8") (pintype "passive"))
    )
    (net (code "59") (name "/CH7-1") (class "Default")
      (node (ref "C53") (pin "2") (pinfunction "2_2") (pintype "passive"))
      (node (ref "D49") (pin "1") (pinfunction "A_1") (pintype "passive"))
      (node (ref "R49") (pin "2") (pinfunction "2_2") (pintype "passive"))
      (node (ref "U7") (pin "4") (pinfunction "S1_4") (pintype "passive"))
    )
    (net (code "60") (name "/CH7-2") (class "Default")
      (node (ref "C54") (pin "2") (pinfunction "2_2") (pintype "passive"))
      (node (ref "D50") (pin "1") (pinfunction "A_1") (pintype "passive"))
      (node (ref "R50") (pin "2") (pinfunction "2_2") (pintype "passive"))
      (node (ref "U7") (pin "5") (pinfunction "S2_5") (pintype "passive"))
    )
    (net (code "61") (name "/CH7-3") (class "Default")
      (node (ref "C55") (pin "2") (pinfunction "2_2") (pintype "passive"))
      (node (ref "D51") (pin "1") (pinfunction "A_1") (pintype "passive"))
      (node (ref "R51") (pin "2") (pinfunction "2_2") (pintype "passive"))
      (node (ref "U7") (pin "6") (pinfunction "S3_6") (pintype "passive"))
    )
    (net (code "62") (name "/CH7-4") (class "Default")
      (node (ref "C56") (pin "2") (pinfunction "2_2") (pintype "passive"))
      (node (ref "D52") (pin "1") (pinfunction "A_1") (pintype "passive"))
      (node (ref "R52") (pin "2") (pinfunction "2_2") (pintype "passive"))
      (node (ref "U7") (pin "7") (pinfunction "S4_7") (pintype "passive"))
    )
    (net (code "63") (name "/CH7-5") (class "Default")
      (node (ref "C57") (pin "2") (pinfunction "2_2") (pintype "passive"))
      (node (ref "D53") (pin "1") (pinfunction "A_1") (pintype "passive"))
      (node (ref "R53") (pin "2") (pinfunction "2_2") (pintype "passive"))
      (node (ref "U7") (pin "12") (pinfunction "S5_12") (pintype "passive"))
    )
    (net (code "64") (name "/CH7-6") (class "Default")
      (node (ref "C58") (pin "2") (pinfunction "2_2") (pintype "passive"))
      (node (ref "D54") (pin "1") (pinfunction "A_1") (pintype "passive"))
      (node (ref "R54") (pin "2") (pinfunction "2_2") (pintype "passive"))
      (node (ref "U7") (pin "11") (pinfunction "S6_11") (pintype "passive"))
    )
    (net (code "65") (name "/CH7-7") (class "Default")
      (node (ref "C59") (pin "2") (pinfunction "2_2") (pintype "passive"))
      (node (ref "D55") (pin "1") (pinfunction "A_1") (pintype "passive"))
      (node (ref "R55") (pin "2") (pinfunction "2_2") (pintype "passive"))
      (node (ref "U7") (pin "10") (pinfunction "S7_10") (pintype "passive"))
    )
    (net (code "66") (name "/CH7-8") (class "Default")
      (node (ref "C60") (pin "2") (pinfunction "2_2") (pintype "passive"))
      (node (ref "D56") (pin "1") (pinfunction "A_1") (pintype "passive"))
      (node (ref "R56") (pin "2") (pinfunction "2_2") (pintype "passive"))
      (node (ref "U7") (pin "9") (pinfunction "S8_9") (pintype "passive"))
    )
    (net (code "67") (name "/CH8") (class "Default")
      (node (ref "P1") (pin "16") (pinfunction "16_16") (pintype "passive"))
      (node (ref "U8") (pin "8") (pinfunction "D_8") (pintype "passive"))
    )
    (net (code "68") (name "/CH8-1") (class "Default")
      (node (ref "C61") (pin "2") (pinfunction "2_2") (pintype "passive"))
      (node (ref "D57") (pin "1") (pinfunction "A_1") (pintype "passive"))
      (node (ref "R57") (pin "2") (pinfunction "2_2") (pintype "passive"))
      (node (ref "U8") (pin "4") (pinfunction "S1_4") (pintype "passive"))
    )
    (net (code "69") (name "/CH8-2") (class "Default")
      (node (ref "C62") (pin "2") (pinfunction "2_2") (pintype "passive"))
      (node (ref "D58") (pin "1") (pinfunction "A_1") (pintype "passive"))
      (node (ref "R58") (pin "2") (pinfunction "2_2") (pintype "passive"))
      (node (ref "U8") (pin "5") (pinfunction "S2_5") (pintype "passive"))
    )
    (net (code "70") (name "/CH8-3") (class "Default")
      (node (ref "C63") (pin "2") (pinfunction "2_2") (pintype "passive"))
      (node (ref "D59") (pin "1") (pinfunction "A_1") (pintype "passive"))
      (node (ref "R59") (pin "2") (pinfunction "2_2") (pintype "passive"))
      (node (ref "U8") (pin "6") (pinfunction "S3_6") (pintype "passive"))
    )
    (net (code "71") (name "/CH8-4") (class "Default")
      (node (ref "C64") (pin "2") (pinfunction "2_2") (pintype "passive"))
      (node (ref "D60") (pin "1") (pinfunction "A_1") (pintype "passive"))
      (node (ref "R60") (pin "2") (pinfunction "2_2") (pintype "passive"))
      (node (ref "U8") (pin "7") (pinfunction "S4_7") (pintype "passive"))
    )
    (net (code "72") (name "/CH8-5") (class "Default")
      (node (ref "C65") (pin "2") (pinfunction "2_2") (pintype "passive"))
      (node (ref "D61") (pin "1") (pinfunction "A_1") (pintype "passive"))
      (node (ref "R61") (pin "2") (pinfunction "2_2") (pintype "passive"))
      (node (ref "U8") (pin "12") (pinfunction "S5_12") (pintype "passive"))
    )
    (net (code "73") (name "/CH8-6") (class "Default")
      (node (ref "C66") (pin "2") (pinfunction "2_2") (pintype "passive"))
      (node (ref "D62") (pin "1") (pinfunction "A_1") (pintype "passive"))
      (node (ref "R62") (pin "2") (pinfunction "2_2") (pintype "passive"))
      (node (ref "U8") (pin "11") (pinfunction "S6_11") (pintype "passive"))
    )
    (net (code "74") (name "/CH8-7") (class "Default")
      (node (ref "C67") (pin "2") (pinfunction "2_2") (pintype "passive"))
      (node (ref "D63") (pin "1") (pinfunction "A_1") (pintype "passive"))
      (node (ref "R63") (pin "2") (pinfunction "2_2") (pintype "passive"))
      (node (ref "U8") (pin "10") (pinfunction "S7_10") (pintype "passive"))
    )
    (net (code "75") (name "/CH8-8") (class "Default")
      (node (ref "C68") (pin "2") (pinfunction "2_2") (pintype "passive"))
      (node (ref "D64") (pin "1") (pinfunction "A_1") (pintype "passive"))
      (node (ref "R64") (pin "2") (pinfunction "2_2") (pintype "passive"))
      (node (ref "U8") (pin "9") (pinfunction "S8_9") (pintype "passive"))
    )
    (net (code "76") (name "/CH9") (class "Default")
      (node (ref "P1") (pin "18") (pinfunction "18_18") (pintype "passive"))
      (node (ref "U9") (pin "8") (pinfunction "D_8") (pintype "passive"))
    )
    (net (code "77") (name "/CH9-1") (class "Default")
      (node (ref "C69") (pin "2") (pinfunction "2_2") (pintype "passive"))
      (node (ref "D65") (pin "1") (pinfunction "A_1") (pintype "passive"))
      (node (ref "R65") (pin "2") (pinfunction "2_2") (pintype "passive"))
      (node (ref "U9") (pin "4") (pinfunction "S1_4") (pintype "passive"))
    )
    (net (code "78") (name "/CH9-2") (class "Default")
      (node (ref "C70") (pin "2") (pinfunction "2_2") (pintype "passive"))
      (node (ref "D66") (pin "1") (pinfunction "A_1") (pintype "passive"))
      (node (ref "R66") (pin "2") (pinfunction "2_2") (pintype "passive"))
      (node (ref "U9") (pin "5") (pinfunction "S2_5") (pintype "passive"))
    )
    (net (code "79") (name "/CH9-3") (class "Default")
      (node (ref "C71") (pin "2") (pinfunction "2_2") (pintype "passive"))
      (node (ref "D67") (pin "1") (pinfunction "A_1") (pintype "passive"))
      (node (ref "R67") (pin "2") (pinfunction "2_2") (pintype "passive"))
      (node (ref "U9") (pin "6") (pinfunction "S3_6") (pintype "passive"))
    )
    (net (code "80") (name "/CH9-4") (class "Default")
      (node (ref "C72") (pin "2") (pinfunction "2_2") (pintype "passive"))
      (node (ref "D68") (pin "1") (pinfunction "A_1") (pintype "passive"))
      (node (ref "R68") (pin "2") (pinfunction "2_2") (pintype "passive"))
      (node (ref "U9") (pin "7") (pinfunction "S4_7") (pintype "passive"))
    )
    (net (code "81") (name "/CH9-5") (class "Default")
      (node (ref "C73") (pin "2") (pinfunction "2_2") (pintype "passive"))
      (node (ref "D69") (pin "1") (pinfunction "A_1") (pintype "passive"))
      (node (ref "R69") (pin "2") (pinfunction "2_2") (pintype "passive"))
      (node (ref "U9") (pin "12") (pinfunction "S5_12") (pintype "passive"))
    )
    (net (code "82") (name "/CH9-6") (class "Default")
      (node (ref "C74") (pin "2") (pinfunction "2_2") (pintype "passive"))
      (node (ref "D70") (pin "1") (pinfunction "A_1") (pintype "passive"))
      (node (ref "R70") (pin "2") (pinfunction "2_2") (pintype "passive"))
      (node (ref "U9") (pin "11") (pinfunction "S6_11") (pintype "passive"))
    )
    (net (code "83") (name "/CH9-7") (class "Default")
      (node (ref "C75") (pin "2") (pinfunction "2_2") (pintype "passive"))
      (node (ref "D71") (pin "1") (pinfunction "A_1") (pintype "passive"))
      (node (ref "R71") (pin "2") (pinfunction "2_2") (pintype "passive"))
      (node (ref "U9") (pin "10") (pinfunction "S7_10") (pintype "passive"))
    )
    (net (code "84") (name "/CH9-8") (class "Default")
      (node (ref "C76") (pin "2") (pinfunction "2_2") (pintype "passive"))
      (node (ref "D72") (pin "1") (pinfunction "A_1") (pintype "passive"))
      (node (ref "R72") (pin "2") (pinfunction "2_2") (pintype "passive"))
      (node (ref "U9") (pin "9") (pinfunction "S8_9") (pintype "passive"))
    )
    (net (code "85") (name "/CH10") (class "Default")
      (node (ref "P1") (pin "20") (pinfunction "20_20") (pintype "passive"))
      (node (ref "U10") (pin "8") (pinfunction "D_8") (pintype "passive"))
    )
    (net (code "86") (name "/CH10-1") (class "Default")
      (node (ref "C77") (pin "2") (pinfunction "2_2") (pintype "passive"))
      (node (ref "D73") (pin "1") (pinfunction "A_1") (pintype "passive"))
      (node (ref "R73") (pin "2") (pinfunction "2_2") (pintype "passive"))
      (node (ref "U10") (pin "4") (pinfunction "S1_4") (pintype "passive"))
    )
    (net (code "87") (name "/CH10-2") (class "Default")
      (node (ref "C78") (pin "2") (pinfunction "2_2") (pintype "passive"))
      (node (ref "D74") (pin "1") (pinfunction "A_1") (pintype "passive"))
      (node (ref "R74") (pin "2") (pinfunction "2_2") (pintype "passive"))
      (node (ref "U10") (pin "5") (pinfunction "S2_5") (pintype "passive"))
    )
    (net (code "88") (name "/CH10-3") (class "Default")
      (node (ref "C79") (pin "2") (pinfunction "2_2") (pintype "passive"))
      (node (ref "D75") (pin "1") (pinfunction "A_1") (pintype "passive"))
      (node (ref "R75") (pin "2") (pinfunction "2_2") (pintype "passive"))
      (node (ref "U10") (pin "6") (pinfunction "S3_6") (pintype "passive"))
    )
    (net (code "89") (name "/CH10-4") (class "Default")
      (node (ref "C80") (pin "2") (pinfunction "2_2") (pintype "passive"))
      (node (ref "D76") (pin "1") (pinfunction "A_1") (pintype "passive"))
      (node (ref "R76") (pin "2") (pinfunction "2_2") (pintype "passive"))
      (node (ref "U10") (pin "7") (pinfunction "S4_7") (pintype "passive"))
    )
    (net (code "90") (name "/CH10-5") (class "Default")
      (node (ref "C81") (pin "2") (pinfunction "2_2") (pintype "passive"))
      (node (ref "D77") (pin "1") (pinfunction "A_1") (pintype "passive"))
      (node (ref "R77") (pin "2") (pinfunction "2_2") (pintype "passive"))
      (node (ref "U10") (pin "12") (pinfunction "S5_12") (pintype "passive"))
    )
    (net (code "91") (name "/CH10-6") (class "Default")
      (node (ref "C82") (pin "2") (pinfunction "2_2") (pintype "passive"))
      (node (ref "D78") (pin "1") (pinfunction "A_1") (pintype "passive"))
      (node (ref "R78") (pin "2") (pinfunction "2_2") (pintype "passive"))
      (node (ref "U10") (pin "11") (pinfunction "S6_11") (pintype "passive"))
    )
    (net (code "92") (name "/CH10-7") (class "Default")
      (node (ref "C83") (pin "2") (pinfunction "2_2") (pintype "passive"))
      (node (ref "D79") (pin "1") (pinfunction "A_1") (pintype "passive"))
      (node (ref "R79") (pin "2") (pinfunction "2_2") (pintype "passive"))
      (node (ref "U10") (pin "10") (pinfunction "S7_10") (pintype "passive"))
    )
    (net (code "93") (name "/CH10-8") (class "Default")
      (node (ref "C84") (pin "2") (pinfunction "2_2") (pintype "passive"))
      (node (ref "D80") (pin "1") (pinfunction "A_1") (pintype "passive"))
      (node (ref "R80") (pin "2") (pinfunction "2_2") (pintype "passive"))
      (node (ref "U10") (pin "9") (pinfunction "S8_9") (pintype "passive"))
    )
    (net (code "94") (name "/CH11") (class "Default")
      (node (ref "P1") (pin "22") (pinfunction "22_22") (pintype "passive"))
      (node (ref "U11") (pin "8") (pinfunction "D_8") (pintype "passive"))
    )
    (net (code "95") (name "/CH11-1") (class "Default")
      (node (ref "C85") (pin "2") (pinfunction "2_2") (pintype "passive"))
      (node (ref "D81") (pin "1") (pinfunction "A_1") (pintype "passive"))
      (node (ref "R81") (pin "2") (pinfunction "2_2") (pintype "passive"))
      (node (ref "U11") (pin "4") (pinfunction "S1_4") (pintype "passive"))
    )
    (net (code "96") (name "/CH11-2") (class "Default")
      (node (ref "C86") (pin "2") (pinfunction "2_2") (pintype "passive"))
      (node (ref "D82") (pin "1") (pinfunction "A_1") (pintype "passive"))
      (node (ref "R82") (pin "2") (pinfunction "2_2") (pintype "passive"))
      (node (ref "U11") (pin "5") (pinfunction "S2_5") (pintype "passive"))
    )
    (net (code "97") (name "/CH11-3") (class "Default")
      (node (ref "C87") (pin "2") (pinfunction "2_2") (pintype "passive"))
      (node (ref "D83") (pin "1") (pinfunction "A_1") (pintype "passive"))
      (node (ref "R83") (pin "2") (pinfunction "2_2") (pintype "passive"))
      (node (ref "U11") (pin "6") (pinfunction "S3_6") (pintype "passive"))
    )
    (net (code "98") (name "/CH11-4") (class "Default")
      (node (ref "C88") (pin "2") (pinfunction "2_2") (pintype "passive"))
      (node (ref "D84") (pin "1") (pinfunction "A_1") (pintype "passive"))
      (node (ref "R84") (pin "2") (pinfunction "2_2") (pintype "passive"))
      (node (ref "U11") (pin "7") (pinfunction "S4_7") (pintype "passive"))
    )
    (net (code "99") (name "/CH11-5") (class "Default")
      (node (ref "C89") (pin "2") (pinfunction "2_2") (pintype "passive"))
      (node (ref "D85") (pin "1") (pinfunction "A_1") (pintype "passive"))
      (node (ref "R85") (pin "2") (pinfunction "2_2") (pintype "passive"))
      (node (ref "U11") (pin "12") (pinfunction "S5_12") (pintype "passive"))
    )
    (net (code "100") (name "/CH11-6") (class "Default")
      (node (ref "C90") (pin "2") (pinfunction "2_2") (pintype "passive"))
      (node (ref "D86") (pin "1") (pinfunction "A_1") (pintype "passive"))
      (node (ref "R86") (pin "2") (pinfunction "2_2") (pintype "passive"))
      (node (ref "U11") (pin "11") (pinfunction "S6_11") (pintype "passive"))
    )
    (net (code "101") (name "/CH11-7") (class "Default")
      (node (ref "C91") (pin "2") (pinfunction "2_2") (pintype "passive"))
      (node (ref "D87") (pin "1") (pinfunction "A_1") (pintype "passive"))
      (node (ref "R87") (pin "2") (pinfunction "2_2") (pintype "passive"))
      (node (ref "U11") (pin "10") (pinfunction "S7_10") (pintype "passive"))
    )
    (net (code "102") (name "/CH11-8") (class "Default")
      (node (ref "C92") (pin "2") (pinfunction "2_2") (pintype "passive"))
      (node (ref "D88") (pin "1") (pinfunction "A_1") (pintype "passive"))
      (node (ref "R88") (pin "2") (pinfunction "2_2") (pintype "passive"))
      (node (ref "U11") (pin "9") (pinfunction "S8_9") (pintype "passive"))
    )
    (net (code "103") (name "/CH12") (class "Default")
      (node (ref "P1") (pin "24") (pinfunction "24_24") (pintype "passive"))
      (node (ref "U12") (pin "8") (pinfunction "D_8") (pintype "passive"))
    )
    (net (code "104") (name "/CH12-1") (class "Default")
      (node (ref "C93") (pin "2") (pinfunction "2_2") (pintype "passive"))
      (node (ref "D89") (pin "1") (pinfunction "A_1") (pintype "passive"))
      (node (ref "R89") (pin "2") (pinfunction "2_2") (pintype "passive"))
      (node (ref "U12") (pin "4") (pinfunction "S1_4") (pintype "passive"))
    )
    (net (code "105") (name "/CH12-2") (class "Default")
      (node (ref "C94") (pin "2") (pinfunction "2_2") (pintype "passive"))
      (node (ref "D90") (pin "1") (pinfunction "A_1") (pintype "passive"))
      (node (ref "R90") (pin "2") (pinfunction "2_2") (pintype "passive"))
      (node (ref "U12") (pin "5") (pinfunction "S2_5") (pintype "passive"))
    )
    (net (code "106") (name "/CH12-3") (class "Default")
      (node (ref "C95") (pin "2") (pinfunction "2_2") (pintype "passive"))
      (node (ref "D91") (pin "1") (pinfunction "A_1") (pintype "passive"))
      (node (ref "R91") (pin "2") (pinfunction "2_2") (pintype "passive"))
      (node (ref "U12") (pin "6") (pinfunction "S3_6") (pintype "passive"))
    )
    (net (code "107") (name "/CH12-4") (class "Default")
      (node (ref "C96") (pin "2") (pinfunction "2_2") (pintype "passive"))
      (node (ref "D92") (pin "1") (pinfunction "A_1") (pintype "passive"))
      (node (ref "R92") (pin "2") (pinfunction "2_2") (pintype "passive"))
      (node (ref "U12") (pin "7") (pinfunction "S4_7") (pintype "passive"))
    )
    (net (code "108") (name "/CH12-5") (class "Default")
      (node (ref "C97") (pin "2") (pinfunction "2_2") (pintype "passive"))
      (node (ref "D93") (pin "1") (pinfunction "A_1") (pintype "passive"))
      (node (ref "R93") (pin "2") (pinfunction "2_2") (pintype "passive"))
      (node (ref "U12") (pin "12") (pinfunction "S5_12") (pintype "passive"))
    )
    (net (code "109") (name "/CH12-6") (class "Default")
      (node (ref "C98") (pin "2") (pinfunction "2_2") (pintype "passive"))
      (node (ref "D94") (pin "1") (pinfunction "A_1") (pintype "passive"))
      (node (ref "R94") (pin "2") (pinfunction "2_2") (pintype "passive"))
      (node (ref "U12") (pin "11") (pinfunction "S6_11") (pintype "passive"))
    )
    (net (code "110") (name "/CH12-7") (class "Default")
      (node (ref "C99") (pin "2") (pinfunction "2_2") (pintype "passive"))
      (node (ref "D95") (pin "1") (pinfunction "A_1") (pintype "passive"))
      (node (ref "R95") (pin "2") (pinfunction "2_2") (pintype "passive"))
      (node (ref "U12") (pin "10") (pinfunction "S7_10") (pintype "passive"))
    )
    (net (code "111") (name "/CH12-8") (class "Default")
      (node (ref "C100") (pin "2") (pinfunction "2_2") (pintype "passive"))
      (node (ref "D96") (pin "1") (pinfunction "A_1") (pintype "passive"))
      (node (ref "R96") (pin "2") (pinfunction "2_2") (pintype "passive"))
      (node (ref "U12") (pin "9") (pinfunction "S8_9") (pintype "passive"))
    )
    (net (code "112") (name "/EN") (class "Default")
      (node (ref "P1") (pin "7") (pinfunction "7_7") (pintype "passive"))
      (node (ref "U1") (pin "2") (pinfunction "EN_2") (pintype "passive"))
      (node (ref "U10") (pin "2") (pinfunction "EN_2") (pintype "passive"))
      (node (ref "U11") (pin "2") (pinfunction "EN_2") (pintype "passive"))
      (node (ref "U12") (pin "2") (pinfunction "EN_2") (pintype "passive"))
      (node (ref "U2") (pin "2") (pinfunction "EN_2") (pintype "passive"))
      (node (ref "U3") (pin "2") (pinfunction "EN_2") (pintype "passive"))
      (node (ref "U4") (pin "2") (pinfunction "EN_2") (pintype "passive"))
      (node (ref "U5") (pin "2") (pinfunction "EN_2") (pintype "passive"))
      (node (ref "U6") (pin "2") (pinfunction "EN_2") (pintype "passive"))
      (node (ref "U7") (pin "2") (pinfunction "EN_2") (pintype "passive"))
      (node (ref "U8") (pin "2") (pinfunction "EN_2") (pintype "passive"))
      (node (ref "U9") (pin "2") (pinfunction "EN_2") (pintype "passive"))
    )
    (net (code "113") (name "GND") (class "Default")
      (node (ref "C1") (pin "1") (pinfunction "1_1") (pintype "passive"))
      (node (ref "C10") (pin "1") (pinfunction "1_1") (pintype "passive"))
      (node (ref "C100") (pin "1") (pinfunction "1_1") (pintype "passive"))
      (node (ref "C11") (pin "1") (pinfunction "1_1") (pintype "passive"))
      (node (ref "C12") (pin "1") (pinfunction "1_1") (pintype "passive"))
      (node (ref "C13") (pin "1") (pinfunction "1_1") (pintype "passive"))
      (node (ref "C14") (pin "1") (pinfunction "1_1") (pintype "passive"))
      (node (ref "C15") (pin "1") (pinfunction "1_1") (pintype "passive"))
      (node (ref "C16") (pin "1") (pinfunction "1_1") (pintype "passive"))
      (node (ref "C17") (pin "1") (pinfunction "1_1") (pintype "passive"))
      (node (ref "C18") (pin "1") (pinfunction "1_1") (pintype "passive"))
      (node (ref "C19") (pin "1") (pinfunction "1_1") (pintype "passive"))
      (node (ref "C2") (pin "1") (pinfunction "1_1") (pintype "passive"))
      (node (ref "C20") (pin "1") (pinfunction "1_1") (pintype "passive"))
      (node (ref "C21") (pin "1") (pinfunction "1_1") (pintype "passive"))
      (node (ref "C22") (pin "1") (pinfunction "1_1") (pintype "passive"))
      (node (ref "C23") (pin "1") (pinfunction "1_1") (pintype "passive"))
      (node (ref "C24") (pin "1") (pinfunction "1_1") (pintype "passive"))
      (node (ref "C25") (pin "1") (pinfunction "1_1") (pintype "passive"))
      (node (ref "C26") (pin "1") (pinfunction "1_1") (pintype "passive"))
      (node (ref "C27") (pin "1") (pinfunction "1_1") (pintype "passive"))
      (node (ref "C28") (pin "1") (pinfunction "1_1") (pintype "passive"))
      (node (ref "C29") (pin "1") (pinfunction "1_1") (pintype "passive"))
      (node (ref "C3") (pin "1") (pinfunction "1_1") (pintype "passive"))
      (node (ref "C30") (pin "1") (pinfunction "1_1") (pintype "passive"))
      (node (ref "C31") (pin "1") (pinfunction "1_1") (pintype "passive"))
      (node (ref "C32") (pin "1") (pinfunction "1_1") (pintype "passive"))
      (node (ref "C33") (pin "1") (pinfunction "1_1") (pintype "passive"))
      (node (ref "C34") (pin "1") (pinfunction "1_1") (pintype "passive"))
      (node (ref "C35") (pin "1") (pinfunction "1_1") (pintype "passive"))
      (node (ref "C36") (pin "1") (pinfunction "1_1") (pintype "passive"))
      (node (ref "C37") (pin "1") (pinfunction "1_1") (pintype "passive"))
      (node (ref "C38") (pin "1") (pinfunction "1_1") (pintype "passive"))
      (node (ref "C39") (pin "1") (pinfunction "1_1") (pintype "passive"))
      (node (ref "C4") (pin "1") (pinfunction "1_1") (pintype "passive"))
      (node (ref "C40") (pin "1") (pinfunction "1_1") (pintype "passive"))
      (node (ref "C41") (pin "1") (pinfunction "1_1") (pintype "passive"))
      (node (ref "C42") (pin "1") (pinfunction "1_1") (pintype "passive"))
      (node (ref "C43") (pin "1") (pinfunction "1_1") (pintype "passive"))
      (node (ref "C44") (pin "1") (pinfunction "1_1") (pintype "passive"))
      (node (ref "C45") (pin "1") (pinfunction "1_1") (pintype "passive"))
      (node (ref "C46") (pin "1") (pinfunction "1_1") (pintype "passive"))
      (node (ref "C47") (pin "1") (pinfunction "1_1") (pintype "passive"))
      (node (ref "C48") (pin "1") (pinfunction "1_1") (pintype "passive"))
      (node (ref "C49") (pin "1") (pinfunction "1_1") (pintype "passive"))
      (node (ref "C5") (pin "1") (pinfunction "1_1") (pintype "passive"))
      (node (ref "C50") (pin "1") (pinfunction "1_1") (pintype "passive"))
      (node (ref "C51") (pin "1") (pinfunction "1_1") (pintype "passive"))
      (node (ref "C52") (pin "1") (pinfunction "1_1") (pintype "passive"))
      (node (ref "C53") (pin "1") (pinfunction "1_1") (pintype "passive"))
      (node (ref "C54") (pin "1") (pinfunction "1_1") (pintype "passive"))
      (node (ref "C55") (pin "1") (pinfunction "1_1") (pintype "passive"))
      (node (ref "C56") (pin "1") (pinfunction "1_1") (pintype "passive"))
      (node (ref "C57") (pin "1") (pinfunction "1_1") (pintype "passive"))
      (node (ref "C58") (pin "1") (pinfunction "1_1") (pintype "passive"))
      (node (ref "C59") (pin "1") (pinfunction "1_1") (pintype "passive"))
      (node (ref "C6") (pin "1") (pinfunction "1_1") (pintype "passive"))
      (node (ref "C60") (pin "1") (pinfunction "1_1") (pintype "passive"))
      (node (ref "C61") (pin "1") (pinfunction "1_1") (pintype "passive"))
      (node (ref "C62") (pin "1") (pinfunction "1_1") (pintype "passive"))
      (node (ref "C63") (pin "1") (pinfunction "1_1") (pintype "passive"))
      (node (ref "C64") (pin "1") (pinfunction "1_1") (pintype "passive"))
      (node (ref "C65") (pin "1") (pinfunction "1_1") (pintype "passive"))
      (node (ref "C66") (pin "1") (pinfunction "1_1") (pintype "passive"))
      (node (ref "C67") (pin "1") (pinfunction "1_1") (pintype "passive"))
      (node (ref "C68") (pin "1") (pinfunction "1_1") (pintype "passive"))
      (node (ref "C69") (pin "1") (pinfunction "1_1") (pintype "passive"))
      (node (ref "C7") (pin "1") (pinfunction "1_1") (pintype "passive"))
      (node (ref "C70") (pin "1") (pinfunction "1_1") (pintype "passive"))
      (node (ref "C71") (pin "1") (pinfunction "1_1") (pintype "passive"))
      (node (ref "C72") (pin "1") (pinfunction "1_1") (pintype "passive"))
      (node (ref "C73") (pin "1") (pinfunction "1_1") (pintype "passive"))
      (node (ref "C74") (pin "1") (pinfunction "1_1") (pintype "passive"))
      (node (ref "C75") (pin "1") (pinfunction "1_1") (pintype "passive"))
      (node (ref "C76") (pin "1") (pinfunction "1_1") (pintype "passive"))
      (node (ref "C77") (pin "1") (pinfunction "1_1") (pintype "passive"))
      (node (ref "C78") (pin "1") (pinfunction "1_1") (pintype "passive"))
      (node (ref "C79") (pin "1") (pinfunction "1_1") (pintype "passive"))
      (node (ref "C8") (pin "1") (pinfunction "1_1") (pintype "passive"))
      (node (ref "C80") (pin "1") (pinfunction "1_1") (pintype "passive"))
      (node (ref "C81") (pin "1") (pinfunction "1_1") (pintype "passive"))
      (node (ref "C82") (pin "1") (pinfunction "1_1") (pintype "passive"))
      (node (ref "C83") (pin "1") (pinfunction "1_1") (pintype "passive"))
      (node (ref "C84") (pin "1") (pinfunction "1_1") (pintype "passive"))
      (node (ref "C85") (pin "1") (pinfunction "1_1") (pintype "passive"))
      (node (ref "C86") (pin "1") (pinfunction "1_1") (pintype "passive"))
      (node (ref "C87") (pin "1") (pinfunction "1_1") (pintype "passive"))
      (node (ref "C88") (pin "1") (pinfunction "1_1") (pintype "passive"))
      (node (ref "C89") (pin "1") (pinfunction "1_1") (pintype "passive"))
      (node (ref "C9") (pin "1") (pinfunction "1_1") (pintype "passive"))
      (node (ref "C90") (pin "1") (pinfunction "1_1") (pintype "passive"))
      (node (ref "C91") (pin "1") (pinfunction "1_1") (pintype "passive"))
      (node (ref "C92") (pin "1") (pinfunction "1_1") (pintype "passive"))
      (node (ref "C93") (pin "1") (pinfunction "1_1") (pintype "passive"))
      (node (ref "C94") (pin "1") (pinfunction "1_1") (pintype "passive"))
      (node (ref "C95") (pin "1") (pinfunction "1_1") (pintype "passive"))
      (node (ref "C96") (pin "1") (pinfunction "1_1") (pintype "passive"))
      (node (ref "C97") (pin "1") (pinfunction "1_1") (pintype "passive"))
      (node (ref "C98") (pin "1") (pinfunction "1_1") (pintype "passive"))
      (node (ref "C99") (pin "1") (pinfunction "1_1") (pintype "passive"))
      (node (ref "P1") (pin "17") (pinfunction "17_17") (pintype "passive"))
      (node (ref "P1") (pin "19") (pinfunction "19_19") (pintype "passive"))
      (node (ref "R1") (pin "1") (pinfunction "1_1") (pintype "passive"))
      (node (ref "R10") (pin "1") (pinfunction "1_1") (pintype "passive"))
      (node (ref "R11") (pin "1") (pinfunction "1_1") (pintype "passive"))
      (node (ref "R12") (pin "1") (pinfunction "1_1") (pintype "passive"))
      (node (ref "R13") (pin "1") (pinfunction "1_1") (pintype "passive"))
      (node (ref "R14") (pin "1") (pinfunction "1_1") (pintype "passive"))
      (node (ref "R15") (pin "1") (pinfunction "1_1") (pintype "passive"))
      (node (ref "R16") (pin "1") (pinfunction "1_1") (pintype "passive"))
      (node (ref "R17") (pin "1") (pinfunction "1_1") (pintype "passive"))
      (node (ref "R18") (pin "1") (pinfunction "1_1") (pintype "passive"))
      (node (ref "R19") (pin "1") (pinfunction "1_1") (pintype "passive"))
      (node (ref "R2") (pin "1") (pinfunction "1_1") (pintype "passive"))
      (node (ref "R20") (pin "1") (pinfunction "1_1") (pintype "passive"))
      (node (ref "R21") (pin "1") (pinfunction "1_1") (pintype "passive"))
      (node (ref "R22") (pin "1") (pinfunction "1_1") (pintype "passive"))
      (node (ref "R23") (pin "1") (pinfunction "1_1") (pintype "passive"))
      (node (ref "R24") (pin "1") (pinfunction "1_1") (pintype "passive"))
      (node (ref "R25") (pin "1") (pinfunction "1_1") (pintype "passive"))
      (node (ref "R26") (pin "1") (pinfunction "1_1") (pintype "passive"))
      (node (ref "R27") (pin "1") (pinfunction "1_1") (pintype "passive"))
      (node (ref "R28") (pin "1") (pinfunction "1_1") (pintype "passive"))
      (node (ref "R29") (pin "1") (pinfunction "1_1") (pintype "passive"))
      (node (ref "R3") (pin "1") (pinfunction "1_1") (pintype "passive"))
      (node (ref "R30") (pin "1") (pinfunction "1_1") (pintype "passive"))
      (node (ref "R31") (pin "1") (pinfunction "1_1") (pintype "passive"))
      (node (ref "R32") (pin "1") (pinfunction "1_1") (pintype "passive"))
      (node (ref "R33") (pin "1") (pinfunction "1_1") (pintype "passive"))
      (node (ref "R34") (pin "1") (pinfunction "1_1") (pintype "passive"))
      (node (ref "R35") (pin "1") (pinfunction "1_1") (pintype "passive"))
      (node (ref "R36") (pin "1") (pinfunction "1_1") (pintype "passive"))
      (node (ref "R37") (pin "1") (pinfunction "1_1") (pintype "passive"))
      (node (ref "R38") (pin "1") (pinfunction "1_1") (pintype "passive"))
      (node (ref "R39") (pin "1") (pinfunction "1_1") (pintype "passive"))
      (node (ref "R4") (pin "1") (pinfunction "1_1") (pintype "passive"))
      (node (ref "R40") (pin "1") (pinfunction "1_1") (pintype "passive"))
      (node (ref "R41") (pin "1") (pinfunction "1_1") (pintype "passive"))
      (node (ref "R42") (pin "1") (pinfunction "1_1") (pintype "passive"))
      (node (ref "R43") (pin "1") (pinfunction "1_1") (pintype "passive"))
      (node (ref "R44") (pin "1") (pinfunction "1_1") (pintype "passive"))
      (node (ref "R45") (pin "1") (pinfunction "1_1") (pintype "passive"))
      (node (ref "R46") (pin "1") (pinfunction "1_1") (pintype "passive"))
      (node (ref "R47") (pin "1") (pinfunction "1_1") (pintype "passive"))
      (node (ref "R48") (pin "1") (pinfunction "1_1") (pintype "passive"))
      (node (ref "R49") (pin "1") (pinfunction "1_1") (pintype "passive"))
      (node (ref "R5") (pin "1") (pinfunction "1_1") (pintype "passive"))
      (node (ref "R50") (pin "1") (pinfunction "1_1") (pintype "passive"))
      (node (ref "R51") (pin "1") (pinfunction "1_1") (pintype "passive"))
      (node (ref "R52") (pin "1") (pinfunction "1_1") (pintype "passive"))
      (node (ref "R53") (pin "1") (pinfunction "1_1") (pintype "passive"))
      (node (ref "R54") (pin "1") (pinfunction "1_1") (pintype "passive"))
      (node (ref "R55") (pin "1") (pinfunction "1_1") (pintype "passive"))
      (node (ref "R56") (pin "1") (pinfunction "1_1") (pintype "passive"))
      (node (ref "R57") (pin "1") (pinfunction "1_1") (pintype "passive"))
      (node (ref "R58") (pin "1") (pinfunction "1_1") (pintype "passive"))
      (node (ref "R59") (pin "1") (pinfunction "1_1") (pintype "passive"))
      (node (ref "R6") (pin "1") (pinfunction "1_1") (pintype "passive"))
      (node (ref "R60") (pin "1") (pinfunction "1_1") (pintype "passive"))
      (node (ref "R61") (pin "1") (pinfunction "1_1") (pintype "passive"))
      (node (ref "R62") (pin "1") (pinfunction "1_1") (pintype "passive"))
      (node (ref "R63") (pin "1") (pinfunction "1_1") (pintype "passive"))
      (node (ref "R64") (pin "1") (pinfunction "1_1") (pintype "passive"))
      (node (ref "R65") (pin "1") (pinfunction "1_1") (pintype "passive"))
      (node (ref "R66") (pin "1") (pinfunction "1_1") (pintype "passive"))
      (node (ref "R67") (pin "1") (pinfunction "1_1") (pintype "passive"))
      (node (ref "R68") (pin "1") (pinfunction "1_1") (pintype "passive"))
      (node (ref "R69") (pin "1") (pinfunction "1_1") (pintype "passive"))
      (node (ref "R7") (pin "1") (pinfunction "1_1") (pintype "passive"))
      (node (ref "R70") (pin "1") (pinfunction "1_1") (pintype "passive"))
      (node (ref "R71") (pin "1") (pinfunction "1_1") (pintype "passive"))
      (node (ref "R72") (pin "1") (pinfunction "1_1") (pintype "passive"))
      (node (ref "R73") (pin "1") (pinfunction "1_1") (pintype "passive"))
      (node (ref "R74") (pin "1") (pinfunction "1_1") (pintype "passive"))
      (node (ref "R75") (pin "1") (pinfunction "1_1") (pintype "passive"))
      (node (ref "R76") (pin "1") (pinfunction "1_1") (pintype "passive"))
      (node (ref "R77") (pin "1") (pinfunction "1_1") (pintype "passive"))
      (node (ref "R78") (pin "1") (pinfunction "1_1") (pintype "passive"))
      (node (ref "R79") (pin "1") (pinfunction "1_1") (pintype "passive"))
      (node (ref "R8") (pin "1") (pinfunction "1_1") (pintype "passive"))
      (node (ref "R80") (pin "1") (pinfunction "1_1") (pintype "passive"))
      (node (ref "R81") (pin "1") (pinfunction "1_1") (pintype "passive"))
      (node (ref "R82") (pin "1") (pinfunction "1_1") (pintype "passive"))
      (node (ref "R83") (pin "1") (pinfunction "1_1") (pintype "passive"))
      (node (ref "R84") (pin "1") (pinfunction "1_1") (pintype "passive"))
      (node (ref "R85") (pin "1") (pinfunction "1_1") (pintype "passive"))
      (node (ref "R86") (pin "1") (pinfunction "1_1") (pintype "passive"))
      (node (ref "R87") (pin "1") (pinfunction "1_1") (pintype "passive"))
      (node (ref "R88") (pin "1") (pinfunction "1_1") (pintype "passive"))
      (node (ref "R89") (pin "1") (pinfunction "1_1") (pintype "passive"))
      (node (ref "R9") (pin "1") (pinfunction "1_1") (pintype "passive"))
      (node (ref "R90") (pin "1") (pinfunction "1_1") (pintype "passive"))
      (node (ref "R91") (pin "1") (pinfunction "1_1") (pintype "passive"))
      (node (ref "R92") (pin "1") (pinfunction "1_1") (pintype "passive"))
      (node (ref "R93") (pin "1") (pinfunction "1_1") (pintype "passive"))
      (node (ref "R94") (pin "1") (pinfunction "1_1") (pintype "passive"))
      (node (ref "R95") (pin "1") (pinfunction "1_1") (pintype "passive"))
      (node (ref "R96") (pin "1") (pinfunction "1_1") (pintype "passive"))
      (node (ref "U1") (pin "14") (pinfunction "GND_14") (pintype "passive"))
      (node (ref "U1") (pin "3") (pinfunction "VSS_3") (pintype "passive"))
      (node (ref "U10") (pin "14") (pinfunction "GND_14") (pintype "passive"))
      (node (ref "U10") (pin "3") (pinfunction "VSS_3") (pintype "passive"))
      (node (ref "U11") (pin "14") (pinfunction "GND_14") (pintype "passive"))
      (node (ref "U11") (pin "3") (pinfunction "VSS_3") (pintype "passive"))
      (node (ref "U12") (pin "14") (pinfunction "GND_14") (pintype "passive"))
      (node (ref "U12") (pin "3") (pinfunction "VSS_3") (pintype "passive"))
      (node (ref "U2") (pin "14") (pinfunction "GND_14") (pintype "passive"))
      (node (ref "U2") (pin "3") (pinfunction "VSS_3") (pintype "passive"))
      (node (ref "U3") (pin "14") (pinfunction "GND_14") (pintype "passive"))
      (node (ref "U3") (pin "3") (pinfunction "VSS_3") (pintype "passive"))
      (node (ref "U4") (pin "14") (pinfunction "GND_14") (pintype "passive"))
      (node (ref "U4") (pin "3") (pinfunction "VSS_3") (pintype "passive"))
      (node (ref "U5") (pin "14") (pinfunction "GND_14") (pintype "passive"))
      (node (ref "U5") (pin "3") (pinfunction "VSS_3") (pintype "passive"))
      (node (ref "U6") (pin "14") (pinfunction "GND_14") (pintype "passive"))
      (node (ref "U6") (pin "3") (pinfunction "VSS_3") (pintype "passive"))
      (node (ref "U7") (pin "14") (pinfunction "GND_14") (pintype "passive"))
      (node (ref "U7") (pin "3") (pinfunction "VSS_3") (pintype "passive"))
      (node (ref "U8") (pin "14") (pinfunction "GND_14") (pintype "passive"))
      (node (ref "U8") (pin "3") (pinfunction "VSS_3") (pintype "passive"))
      (node (ref "U9") (pin "14") (pinfunction "GND_14") (pintype "passive"))
      (node (ref "U9") (pin "3") (pinfunction "VSS_3") (pintype "passive"))
    )
    (net (code "114") (name "VCC3.3") (class "Default")
      (node (ref "C3") (pin "2") (pinfunction "2_2") (pintype "passive"))
      (node (ref "C4") (pin "2") (pinfunction "2_2") (pintype "passive"))
      (node (ref "D1") (pin "2") (pinfunction "K_2") (pintype "passive"))
      (node (ref "D10") (pin "2") (pinfunction "K_2") (pintype "passive"))
      (node (ref "D11") (pin "2") (pinfunction "K_2") (pintype "passive"))
      (node (ref "D12") (pin "2") (pinfunction "K_2") (pintype "passive"))
      (node (ref "D13") (pin "2") (pinfunction "K_2") (pintype "passive"))
      (node (ref "D14") (pin "2") (pinfunction "K_2") (pintype "passive"))
      (node (ref "D15") (pin "2") (pinfunction "K_2") (pintype "passive"))
      (node (ref "D16") (pin "2") (pinfunction "K_2") (pintype "passive"))
      (node (ref "D17") (pin "2") (pinfunction "K_2") (pintype "passive"))
      (node (ref "D18") (pin "2") (pinfunction "K_2") (pintype "passive"))
      (node (ref "D19") (pin "2") (pinfunction "K_2") (pintype "passive"))
      (node (ref "D2") (pin "2") (pinfunction "K_2") (pintype "passive"))
      (node (ref "D20") (pin "2") (pinfunction "K_2") (pintype "passive"))
      (node (ref "D21") (pin "2") (pinfunction "K_2") (pintype "passive"))
      (node (ref "D22") (pin "2") (pinfunction "K_2") (pintype "passive"))
      (node (ref "D23") (pin "2") (pinfunction "K_2") (pintype "passive"))
      (node (ref "D24") (pin "2") (pinfunction "K_2") (pintype "passive"))
      (node (ref "D25") (pin "2") (pinfunction "K_2") (pintype "passive"))
      (node (ref "D26") (pin "2") (pinfunction "K_2") (pintype "passive"))
      (node (ref "D27") (pin "2") (pinfunction "K_2") (pintype "passive"))
      (node (ref "D28") (pin "2") (pinfunction "K_2") (pintype "passive"))
      (node (ref "D29") (pin "2") (pinfunction "K_2") (pintype "passive"))
      (node (ref "D3") (pin "2") (pinfunction "K_2") (pintype "passive"))
      (node (ref "D30") (pin "2") (pinfunction "K_2") (pintype "passive"))
      (node (ref "D31") (pin "2") (pinfunction "K_2") (pintype "passive"))
      (node (ref "D32") (pin "2") (pinfunction "K_2") (pintype "passive"))
      (node (ref "D33") (pin "2") (pinfunction "K_2") (pintype "passive"))
      (node (ref "D34") (pin "2") (pinfunction "K_2") (pintype "passive"))
      (node (ref "D35") (pin "2") (pinfunction "K_2") (pintype "passive"))
      (node (ref "D36") (pin "2") (pinfunction "K_2") (pintype "passive"))
      (node (ref "D37") (pin "2") (pinfunction "K_2") (pintype "passive"))
      (node (ref "D38") (pin "2") (pinfunction "K_2") (pintype "passive"))
      (node (ref "D39") (pin "2") (pinfunction "K_2") (pintype "passive"))
      (node (ref "D4") (pin "2") (pinfunction "K_2") (pintype "passive"))
      (node (ref "D40") (pin "2") (pinfunction "K_2") (pintype "passive"))
      (node (ref "D41") (pin "2") (pinfunction "K_2") (pintype "passive"))
      (node (ref "D42") (pin "2") (pinfunction "K_2") (pintype "passive"))
      (node (ref "D43") (pin "2") (pinfunction "K_2") (pintype "passive"))
      (node (ref "D44") (pin "2") (pinfunction "K_2") (pintype "passive"))
      (node (ref "D45") (pin "2") (pinfunction "K_2") (pintype "passive"))
      (node (ref "D46") (pin "2") (pinfunction "K_2") (pintype "passive"))
      (node (ref "D47") (pin "2") (pinfunction "K_2") (pintype "passive"))
      (node (ref "D48") (pin "2") (pinfunction "K_2") (pintype "passive"))
      (node (ref "D49") (pin "2") (pinfunction "K_2") (pintype "passive"))
      (node (ref "D5") (pin "2") (pinfunction "K_2") (pintype "passive"))
      (node (ref "D50") (pin "2") (pinfunction "K_2") (pintype "passive"))
      (node (ref "D51") (pin "2") (pinfunction "K_2") (pintype "passive"))
      (node (ref "D52") (pin "2") (pinfunction "K_2") (pintype "passive"))
      (node (ref "D53") (pin "2") (pinfunction "K_2") (pintype "passive"))
      (node (ref "D54") (pin "2") (pinfunction "K_2") (pintype "passive"))
      (node (ref "D55") (pin "2") (pinfunction "K_2") (pintype "passive"))
      (node (ref "D56") (pin "2") (pinfunction "K_2") (pintype "passive"))
      (node (ref "D57") (pin "2") (pinfunction "K_2") (pintype "passive"))
      (node (ref "D58") (pin "2") (pinfunction "K_2") (pintype "passive"))
      (node (ref "D59") (pin "2") (pinfunction "K_2") (pintype "passive"))
      (node (ref "D6") (pin "2") (pinfunction "K_2") (pintype "passive"))
      (node (ref "D60") (pin "2") (pinfunction "K_2") (pintype "passive"))
      (node (ref "D61") (pin "2") (pinfunction "K_2") (pintype "passive"))
      (node (ref "D62") (pin "2") (pinfunction "K_2") (pintype "passive"))
      (node (ref "D63") (pin "2") (pinfunction "K_2") (pintype "passive"))
      (node (ref "D64") (pin "2") (pinfunction "K_2") (pintype "passive"))
      (node (ref "D65") (pin "2") (pinfunction "K_2") (pintype "passive"))
      (node (ref "D66") (pin "2") (pinfunction "K_2") (pintype "passive"))
      (node (ref "D67") (pin "2") (pinfunction "K_2") (pintype "passive"))
      (node (ref "D68") (pin "2") (pinfunction "K_2") (pintype "passive"))
      (node (ref "D69") (pin "2") (pinfunction "K_2") (pintype "passive"))
      (node (ref "D7") (pin "2") (pinfunction "K_2") (pintype "passive"))
      (node (ref "D70") (pin "2") (pinfunction "K_2") (pintype "passive"))
      (node (ref "D71") (pin "2") (pinfunction "K_2") (pintype "passive"))
      (node (ref "D72") (pin "2") (pinfunction "K_2") (pintype "passive"))
      (node (ref "D73") (pin "2") (pinfunction "K_2") (pintype "passive"))
      (node (ref "D74") (pin "2") (pinfunction "K_2") (pintype "passive"))
      (node (ref "D75") (pin "2") (pinfunction "K_2") (pintype "passive"))
      (node (ref "D76") (pin "2") (pinfunction "K_2") (pintype "passive"))
      (node (ref "D77") (pin "2") (pinfunction "K_2") (pintype "passive"))
      (node (ref "D78") (pin "2") (pinfunction "K_2") (pintype "passive"))
      (node (ref "D79") (pin "2") (pinfunction "K_2") (pintype "passive"))
      (node (ref "D8") (pin "2") (pinfunction "K_2") (pintype "passive"))
      (node (ref "D80") (pin "2") (pinfunction "K_2") (pintype "passive"))
      (node (ref "D81") (pin "2") (pinfunction "K_2") (pintype "passive"))
      (node (ref "D82") (pin "2") (pinfunction "K_2") (pintype "passive"))
      (node (ref "D83") (pin "2") (pinfunction "K_2") (pintype "passive"))
      (node (ref "D84") (pin "2") (pinfunction "K_2") (pintype "passive"))
      (node (ref "D85") (pin "2") (pinfunction "K_2") (pintype "passive"))
      (node (ref "D86") (pin "2") (pinfunction "K_2") (pintype "passive"))
      (node (ref "D87") (pin "2") (pinfunction "K_2") (pintype "passive"))
      (node (ref "D88") (pin "2") (pinfunction "K_2") (pintype "passive"))
      (node (ref "D89") (pin "2") (pinfunction "K_2") (pintype "passive"))
      (node (ref "D9") (pin "2") (pinfunction "K_2") (pintype "passive"))
      (node (ref "D90") (pin "2") (pinfunction "K_2") (pintype "passive"))
      (node (ref "D91") (pin "2") (pinfunction "K_2") (pintype "passive"))
      (node (ref "D92") (pin "2") (pinfunction "K_2") (pintype "passive"))
      (node (ref "D93") (pin "2") (pinfunction "K_2") (pintype "passive"))
      (node (ref "D94") (pin "2") (pinfunction "K_2") (pintype "passive"))
      (node (ref "D95") (pin "2") (pinfunction "K_2") (pintype "passive"))
      (node (ref "D96") (pin "2") (pinfunction "K_2") (pintype "passive"))
      (node (ref "P1") (pin "21") (pinfunction "21_21") (pintype "passive"))
      (node (ref "P1") (pin "23") (pinfunction "23_23") (pintype "passive"))
    )
    (net (code "115") (name "VCC5V") (class "Default")
      (node (ref "C1") (pin "2") (pinfunction "2_2") (pintype "passive"))
      (node (ref "C2") (pin "2") (pinfunction "2_2") (pintype "passive"))
      (node (ref "P1") (pin "13") (pinfunction "13_13") (pintype "passive"))
      (node (ref "P1") (pin "15") (pinfunction "15_15") (pintype "passive"))
      (node (ref "U1") (pin "13") (pinfunction "VDD_13") (pintype "passive"))
      (node (ref "U10") (pin "13") (pinfunction "VDD_13") (pintype "passive"))
      (node (ref "U11") (pin "13") (pinfunction "VDD_13") (pintype "passive"))
      (node (ref "U12") (pin "13") (pinfunction "VDD_13") (pintype "passive"))
      (node (ref "U2") (pin "13") (pinfunction "VDD_13") (pintype "passive"))
      (node (ref "U3") (pin "13") (pinfunction "VDD_13") (pintype "passive"))
      (node (ref "U4") (pin "13") (pinfunction "VDD_13") (pintype "passive"))
      (node (ref "U5") (pin "13") (pinfunction "VDD_13") (pintype "passive"))
      (node (ref "U6") (pin "13") (pinfunction "VDD_13") (pintype "passive"))
      (node (ref "U7") (pin "13") (pinfunction "VDD_13") (pintype "passive"))
      (node (ref "U8") (pin "13") (pinfunction "VDD_13") (pintype "passive"))
      (node (ref "U9") (pin "13") (pinfunction "VDD_13") (pintype "passive"))
    )
    (net (code "116") (name "unconnected-(P1-Pad9)") (class "Default")
      (node (ref "P1") (pin "9") (pinfunction "9_9") (pintype "passive"))
    )
    (net (code "117") (name "unconnected-(P1-Pad11)") (class "Default")
      (node (ref "P1") (pin "11") (pinfunction "11_11") (pintype "passive"))
    )
  )
)
